# SCH-HC15C_REV3_PG3.net
KiCad netlist of a schematic drawn in Altium Designer
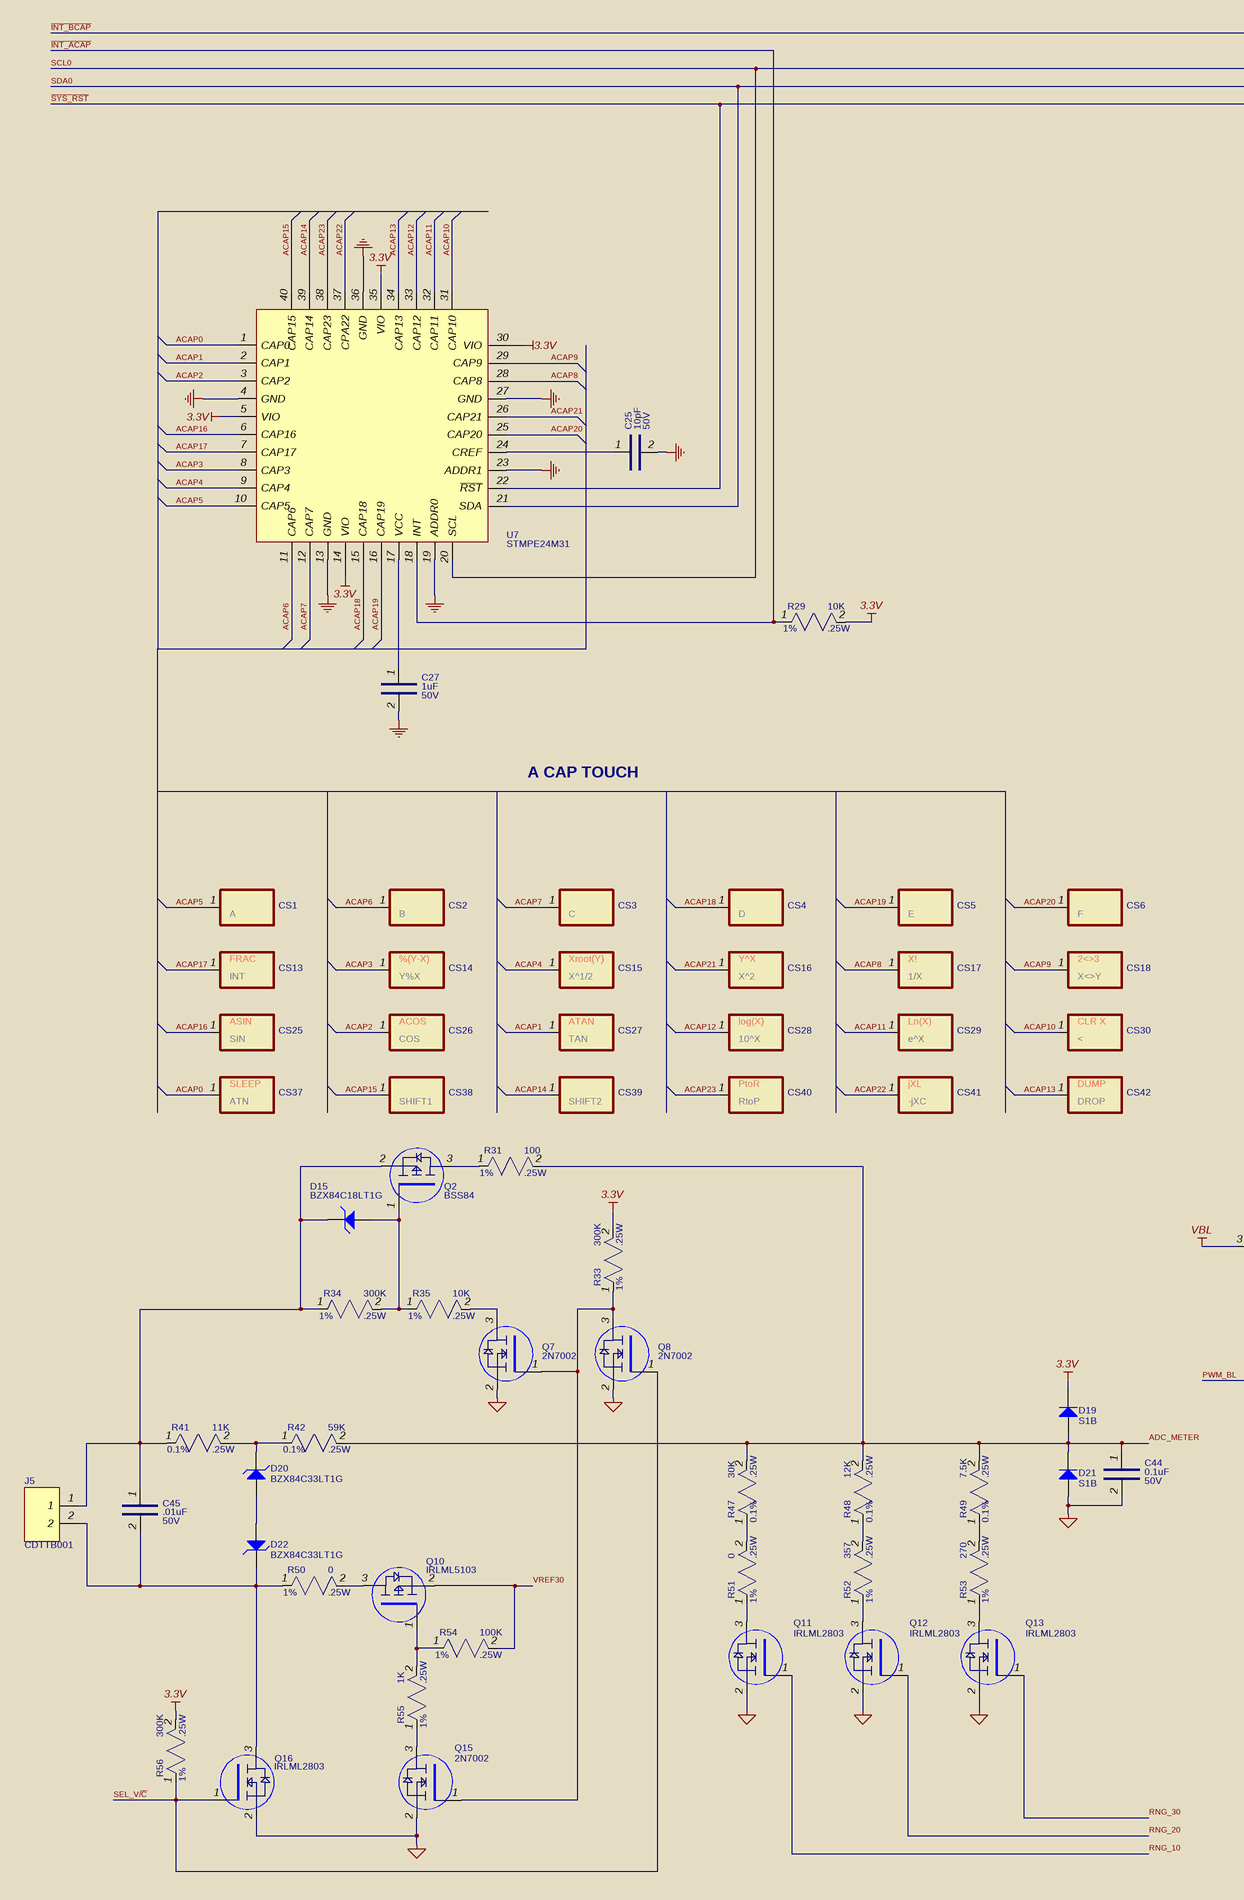
[diagram p0: SCH-HC15C_REV3_PG3.SchDoc, left]
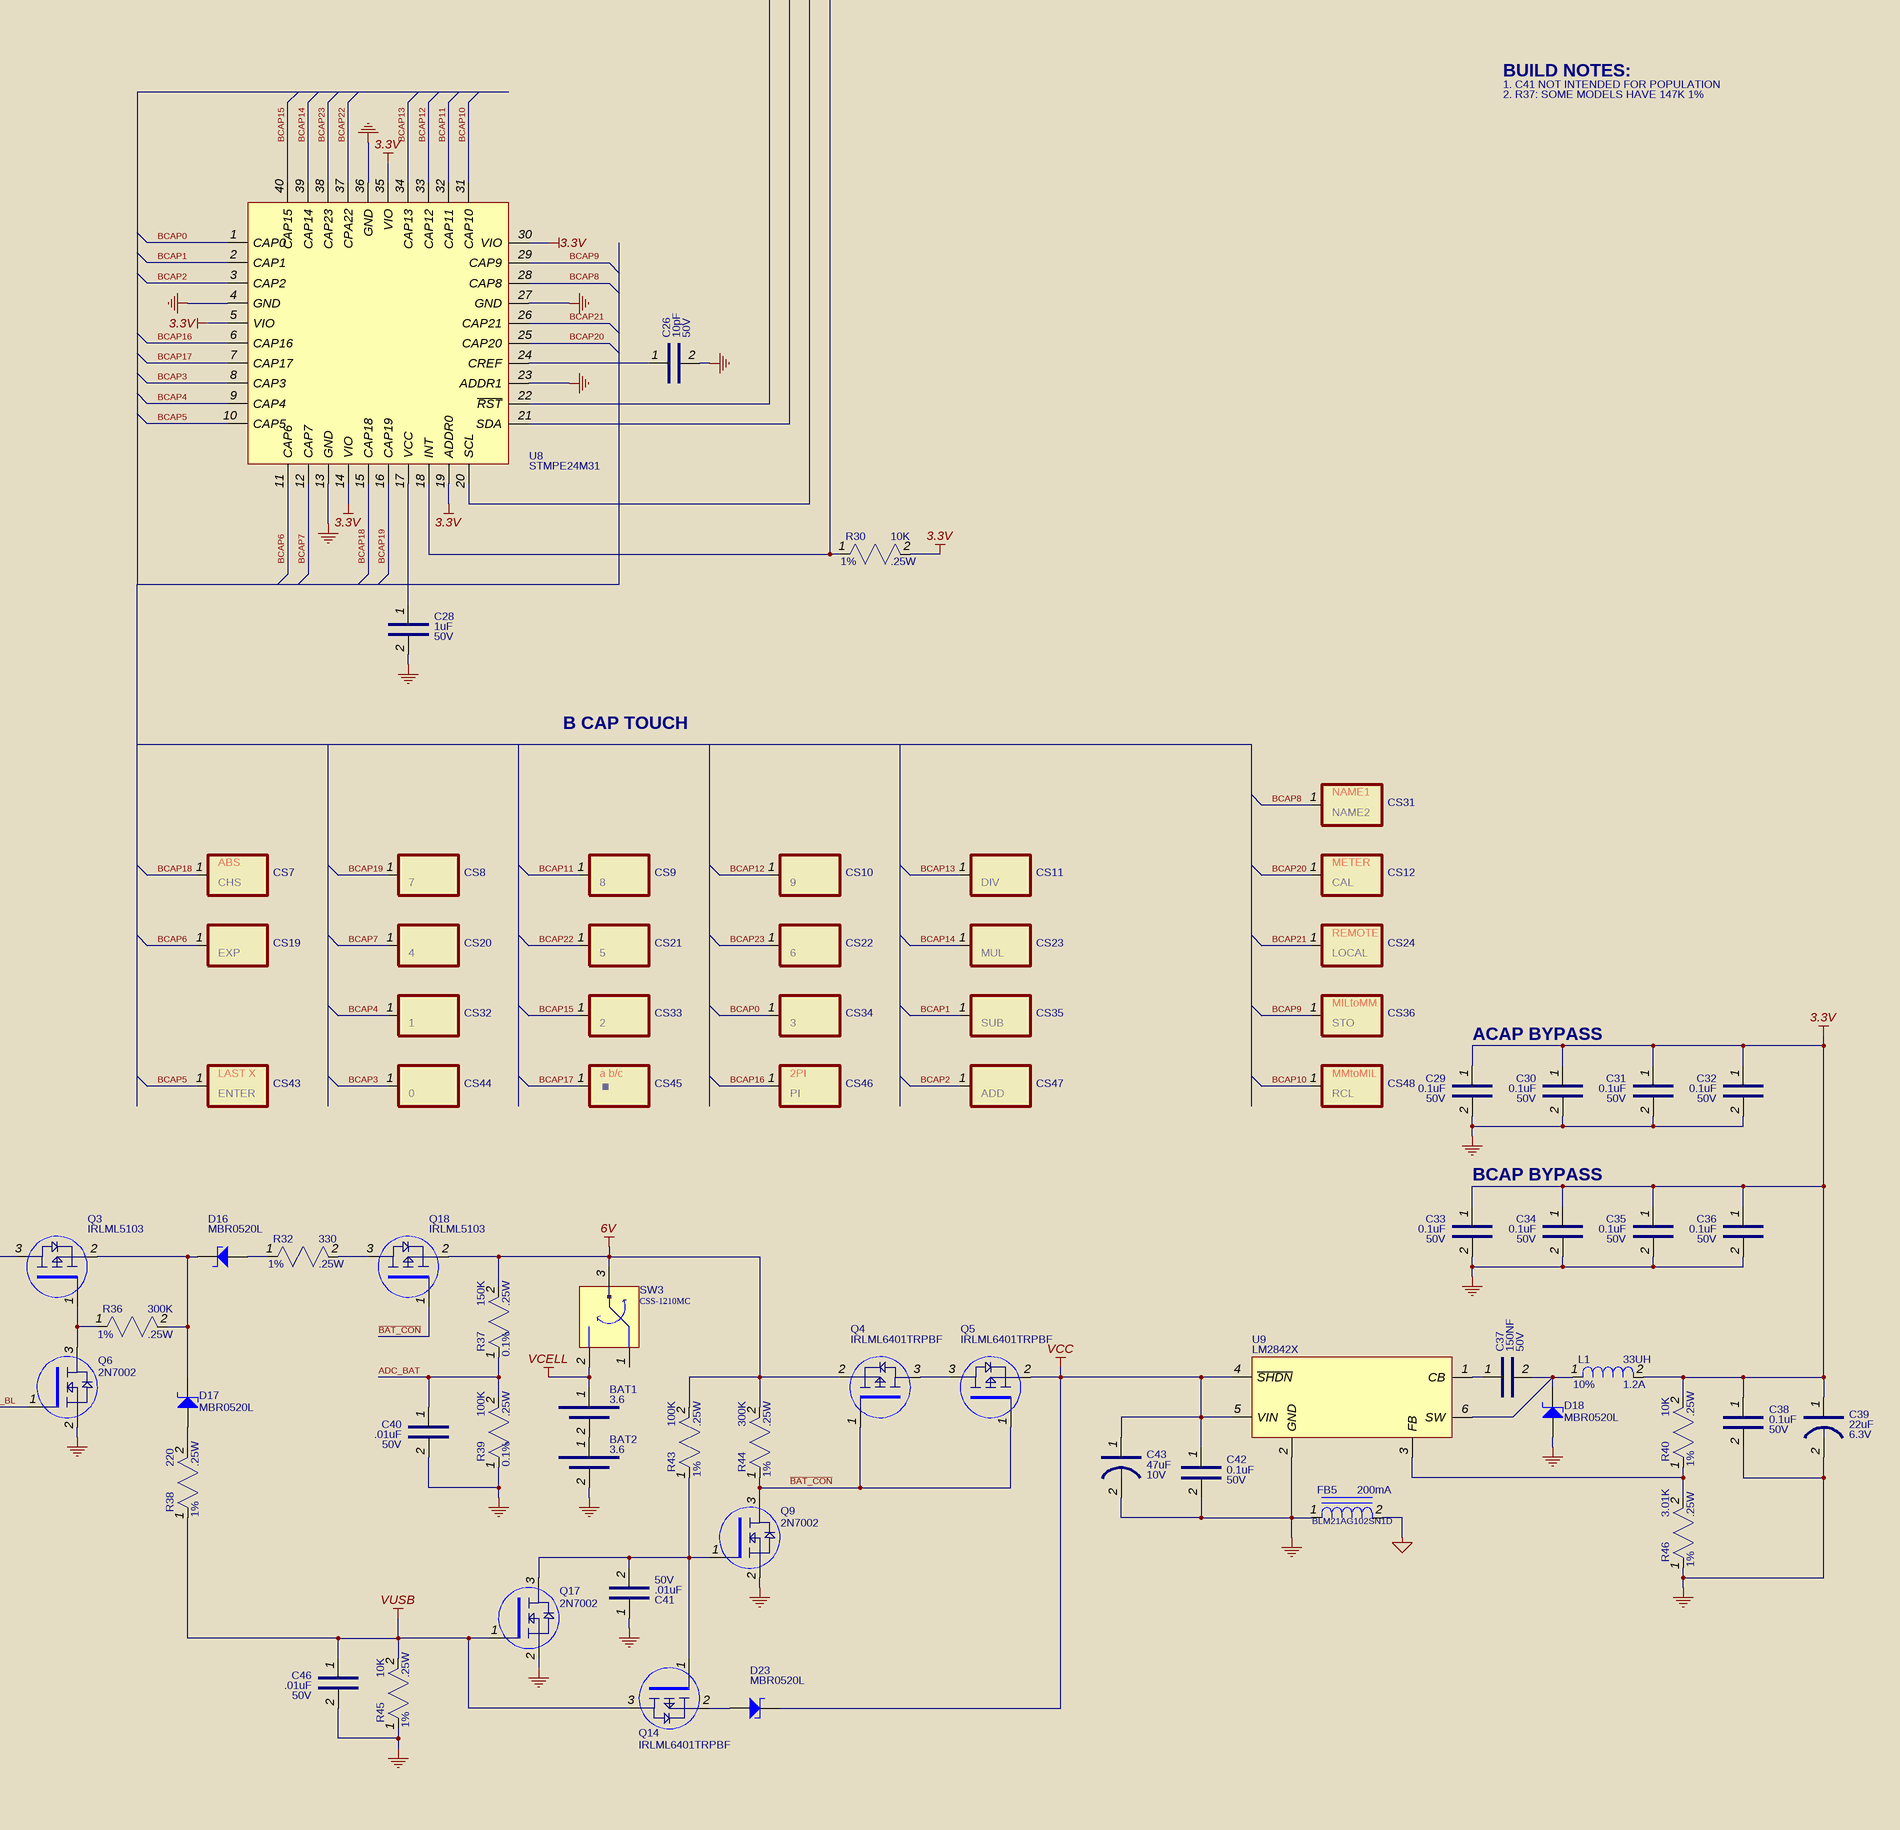
[diagram p1: SCH-HC15C_REV3_PG3.SchDoc, right]

(export (version "E")
  (design (tool "Eeschema 10.0.6"))
  (components
    (comp (ref "BAT1")
      (value "CDEVA00082_3")
      (footprint "KEYSTONE_108")
      (description "BAT HOLDER 1/2AA TH ROHS")
      (fields (field (name "MFG") "KEYSTONE") (field (name "VOLTAGE") "3.6"))
      (libsource (lib "HabLib") (part "CDEVA00082_3"))
    )
    (comp (ref "BAT2")
      (value "CDEVA00082_3")
      (footprint "KEYSTONE_108")
      (description "BAT HOLDER 1/2AA TH ROHS")
      (fields (field (name "MFG") "KEYSTONE") (field (name "VOLTAGE") "3.6"))
      (libsource (lib "HabLib") (part "CDEVA00082_3"))
    )
    (comp (ref "C25")
      (value "10pF")
      (footprint "3216[1206] - TAN COLOR")
      (description "CAP, CERAMIC, NPO, 10PF, 50V, 1206, 5%, RoHS")
      (fields (field (name "MFG") "AVX") (field (name "TOLERANCE") "10%") (field (name "VOLTAGE") "50V"))
      (libsource (lib "HabLib") (part "CDECA00143"))
    )
    (comp (ref "C26")
      (value "10pF")
      (footprint "3216[1206] - TAN COLOR")
      (description "CAP, CERAMIC, NPO, 10PF, 50V, 1206, 5%, RoHS")
      (fields (field (name "MFG") "AVX") (field (name "TOLERANCE") "10%") (field (name "VOLTAGE") "50V"))
      (libsource (lib "HabLib") (part "CDECA00143"))
    )
    (comp (ref "C27")
      (value "1uF")
      (footprint "3225[1210]")
      (description "CAP, CERAMIC CHIP 1UF 10% 50V X7R ROHS")
      (fields (field (name "MFG") "AVX") (field (name "TOLERANCE") "10%") (field (name "VOLTAGE") "50V"))
      (libsource (lib "HabLib") (part "CDECA00122"))
    )
    (comp (ref "C28")
      (value "1uF")
      (footprint "3225[1210]")
      (description "CAP, CERAMIC CHIP 1UF 10% 50V X7R ROHS")
      (fields (field (name "MFG") "AVX") (field (name "TOLERANCE") "10%") (field (name "VOLTAGE") "50V"))
      (libsource (lib "HabLib") (part "CDECA00122"))
    )
    (comp (ref "C29")
      (value "0.1uF")
      (footprint "3216[1206] - TAN COLOR")
      (description "CAP, CERAMIC CHIP 0.1UF 10% 50V X7R ROHS")
      (fields (field (name "MFG") "AVX") (field (name "TOLERANCE") "10%") (field (name "VOLTAGE") "50V"))
      (libsource (lib "HabLib") (part "CDECA00070"))
    )
    (comp (ref "C30")
      (value "0.1uF")
      (footprint "3216[1206] - TAN COLOR")
      (description "CAP, CERAMIC CHIP 0.1UF 10% 50V X7R ROHS")
      (fields (field (name "MFG") "AVX") (field (name "TOLERANCE") "10%") (field (name "VOLTAGE") "50V"))
      (libsource (lib "HabLib") (part "CDECA00070"))
    )
    (comp (ref "C31")
      (value "0.1uF")
      (footprint "3216[1206] - TAN COLOR")
      (description "CAP, CERAMIC CHIP 0.1UF 10% 50V X7R ROHS")
      (fields (field (name "MFG") "AVX") (field (name "TOLERANCE") "10%") (field (name "VOLTAGE") "50V"))
      (libsource (lib "HabLib") (part "CDECA00070"))
    )
    (comp (ref "C32")
      (value "0.1uF")
      (footprint "3216[1206] - TAN COLOR")
      (description "CAP, CERAMIC CHIP 0.1UF 10% 50V X7R ROHS")
      (fields (field (name "MFG") "AVX") (field (name "TOLERANCE") "10%") (field (name "VOLTAGE") "50V"))
      (libsource (lib "HabLib") (part "CDECA00070"))
    )
    (comp (ref "C33")
      (value "0.1uF")
      (footprint "3216[1206] - TAN COLOR")
      (description "CAP, CERAMIC CHIP 0.1UF 10% 50V X7R ROHS")
      (fields (field (name "MFG") "AVX") (field (name "TOLERANCE") "10%") (field (name "VOLTAGE") "50V"))
      (libsource (lib "HabLib") (part "CDECA00070"))
    )
    (comp (ref "C34")
      (value "0.1uF")
      (footprint "3216[1206] - TAN COLOR")
      (description "CAP, CERAMIC CHIP 0.1UF 10% 50V X7R ROHS")
      (fields (field (name "MFG") "AVX") (field (name "TOLERANCE") "10%") (field (name "VOLTAGE") "50V"))
      (libsource (lib "HabLib") (part "CDECA00070"))
    )
    (comp (ref "C35")
      (value "0.1uF")
      (footprint "3216[1206] - TAN COLOR")
      (description "CAP, CERAMIC CHIP 0.1UF 10% 50V X7R ROHS")
      (fields (field (name "MFG") "AVX") (field (name "TOLERANCE") "10%") (field (name "VOLTAGE") "50V"))
      (libsource (lib "HabLib") (part "CDECA00070"))
    )
    (comp (ref "C36")
      (value "0.1uF")
      (footprint "3216[1206] - TAN COLOR")
      (description "CAP, CERAMIC CHIP 0.1UF 10% 50V X7R ROHS")
      (fields (field (name "MFG") "AVX") (field (name "TOLERANCE") "10%") (field (name "VOLTAGE") "50V"))
      (libsource (lib "HabLib") (part "CDECA00070"))
    )
    (comp (ref "C37")
      (value "150NF")
      (footprint "3216[1206] - TAN COLOR")
      (description "CAP, CERAMIC, X7R, 150NF, 50V, 1206, 10%, RoHS")
      (fields (field (name "MFG") "KEMET") (field (name "TOLERANCE") "10%") (field (name "VOLTAGE") "50V"))
      (libsource (lib "HabLib") (part "CDECA00143_1"))
    )
    (comp (ref "C38")
      (value "0.1uF")
      (footprint "3216[1206] - TAN COLOR")
      (description "CAP, CERAMIC CHIP 0.1UF 10% 50V X7R ROHS")
      (fields (field (name "MFG") "AVX") (field (name "TOLERANCE") "10%") (field (name "VOLTAGE") "50V"))
      (libsource (lib "HabLib") (part "CDECA00070"))
    )
    (comp (ref "C39")
      (value "22uF")
      (footprint "3216[1206] - TANTALUM")
      (description "CAP, TANT, 22UF, 6.3V, 20%, LOW ESR, 1206ROHS")
      (fields (field (name "MFG") "AVX") (field (name "TOLERANCE") "20%") (field (name "VOLTAGE") "6.3V"))
      (libsource (lib "HabLib") (part "CDECA00139_1"))
    )
    (comp (ref "C40")
      (value ".01uF")
      (footprint "3216[1206] - TAN COLOR")
      (description "CAP, CERAMIC CHIP 0.01UF 10% 50V X7R ROHS")
      (fields
        (field (name "MFG") "PANASONIC")
        (field (name "TOLERANCE") "10%")
        (field (name "VOLTAGE") "50V")
      )
      (libsource (lib "HabLib") (part "CDECA00085"))
    )
    (comp (ref "C41")
      (value ".01uF")
      (footprint "3216[1206] - TAN COLOR")
      (description "CAP, CERAMIC CHIP 0.01UF 10% 50V X7R ROHS")
      (fields
        (field (name "MFG") "PANASONIC")
        (field (name "TOLERANCE") "10%")
        (field (name "VOLTAGE") "50V")
      )
      (libsource (lib "HabLib") (part "CDECA00085"))
    )
    (comp (ref "C42")
      (value "0.1uF")
      (footprint "3216[1206] - TAN COLOR")
      (description "CAP, CERAMIC CHIP 0.1UF 10% 50V X7R ROHS")
      (fields (field (name "MFG") "AVX") (field (name "TOLERANCE") "10%") (field (name "VOLTAGE") "50V"))
      (libsource (lib "HabLib") (part "CDECA00070"))
    )
    (comp (ref "C43")
      (value "47uF")
      (footprint "CAP_TANT_3528")
      (description "CAP, TANT, 47UF, 25V, 20%, 3528 ROHS")
      (fields (field (name "MFG") "AVX") (field (name "TOLERANCE") "20%") (field (name "VOLTAGE") "10V"))
      (libsource (lib "HabLib") (part "CDECA00110_1"))
    )
    (comp (ref "C44")
      (value "0.1uF")
      (footprint "3216[1206] - TAN COLOR")
      (description "CAP, CERAMIC CHIP 0.1UF 10% 50V X7R ROHS")
      (fields (field (name "MFG") "AVX") (field (name "TOLERANCE") "10%") (field (name "VOLTAGE") "50V"))
      (libsource (lib "HabLib") (part "CDECA00070"))
    )
    (comp (ref "C45")
      (value ".01uF")
      (footprint "3216[1206] - TAN COLOR")
      (description "CAP, CERAMIC CHIP 0.01UF 10% 50V X7R ROHS")
      (fields
        (field (name "MFG") "PANASONIC")
        (field (name "TOLERANCE") "10%")
        (field (name "VOLTAGE") "50V")
      )
      (libsource (lib "") (part "CDECA00085_1"))
    )
    (comp (ref "C46")
      (value ".01uF")
      (footprint "3216[1206] - TAN COLOR")
      (description "CAP, CERAMIC CHIP 0.01UF 10% 50V X7R ROHS")
      (fields
        (field (name "MFG") "PANASONIC")
        (field (name "TOLERANCE") "10%")
        (field (name "VOLTAGE") "50V")
      )
      (libsource (lib "HabLib") (part "CDECA00085"))
    )
    (comp (ref "CS1")
      (value "CAP_SENSOR")
      (footprint "CAPTOUCH1_10X10")
      (description "CAP SENSOR FOR PCB")
      (fields (field (name "VALUE2") "A") (field (name "PUBLISHER") "Altium Limited"))
      (libsource (lib "HabLib") (part "CAP_SENSOR"))
    )
    (comp (ref "CS2")
      (value "CAP_SENSOR")
      (footprint "CAPTOUCH1_10X10")
      (description "CAP SENSOR FOR PCB")
      (fields (field (name "VALUE2") "B") (field (name "PUBLISHER") "Altium Limited"))
      (libsource (lib "HabLib") (part "CAP_SENSOR"))
    )
    (comp (ref "CS3")
      (value "CAP_SENSOR")
      (footprint "CAPTOUCH1_10X10")
      (description "CAP SENSOR FOR PCB")
      (fields (field (name "VALUE2") "C") (field (name "PUBLISHER") "Altium Limited"))
      (libsource (lib "HabLib") (part "CAP_SENSOR"))
    )
    (comp (ref "CS4")
      (value "CAP_SENSOR")
      (footprint "CAPTOUCH1_10X10")
      (description "CAP SENSOR FOR PCB")
      (fields (field (name "VALUE2") "D") (field (name "PUBLISHER") "Altium Limited"))
      (libsource (lib "HabLib") (part "CAP_SENSOR"))
    )
    (comp (ref "CS5")
      (value "CAP_SENSOR")
      (footprint "CAPTOUCH1_10X10")
      (description "CAP SENSOR FOR PCB")
      (fields (field (name "VALUE2") "E") (field (name "PUBLISHER") "Altium Limited"))
      (libsource (lib "HabLib") (part "CAP_SENSOR"))
    )
    (comp (ref "CS6")
      (value "CAP_SENSOR")
      (footprint "CAPTOUCH1_10X10")
      (description "CAP SENSOR FOR PCB")
      (fields (field (name "VALUE2") "F") (field (name "PUBLISHER") "Altium Limited"))
      (libsource (lib "HabLib") (part "CAP_SENSOR"))
    )
    (comp (ref "CS7")
      (value "ABS")
      (footprint "CAPTOUCH1_10X10")
      (description "CAP SENSOR FOR PCB")
      (fields
        (field (name "VALUE2") "CHS")
        (field (name "Comment") "CAP_SENSOR")
        (field (name "PUBLISHER") "Altium Limited")
      )
      (libsource (lib "HabLib") (part "CAP_SENSOR"))
    )
    (comp (ref "CS8")
      (value "CAP_SENSOR")
      (footprint "CAPTOUCH1_10X10")
      (description "CAP SENSOR FOR PCB")
      (fields (field (name "VALUE2") "7") (field (name "PUBLISHER") "Altium Limited"))
      (libsource (lib "HabLib") (part "CAP_SENSOR"))
    )
    (comp (ref "CS9")
      (value "CAP_SENSOR")
      (footprint "CAPTOUCH1_10X10")
      (description "CAP SENSOR FOR PCB")
      (fields (field (name "VALUE2") "8") (field (name "PUBLISHER") "Altium Limited"))
      (libsource (lib "HabLib") (part "CAP_SENSOR"))
    )
    (comp (ref "CS10")
      (value "CAP_SENSOR")
      (footprint "CAPTOUCH1_10X10")
      (description "CAP SENSOR FOR PCB")
      (fields (field (name "VALUE2") "9") (field (name "PUBLISHER") "Altium Limited"))
      (libsource (lib "HabLib") (part "CAP_SENSOR"))
    )
    (comp (ref "CS11")
      (value "CAP_SENSOR")
      (footprint "CAPTOUCH1_10X10")
      (description "CAP SENSOR FOR PCB")
      (fields (field (name "VALUE2") "DIV") (field (name "PUBLISHER") "Altium Limited"))
      (libsource (lib "HabLib") (part "CAP_SENSOR"))
    )
    (comp (ref "CS12")
      (value "METER")
      (footprint "CAPTOUCH1_10X10")
      (description "CAP SENSOR FOR PCB")
      (fields
        (field (name "VALUE2") "CAL")
        (field (name "Comment") "CAP_SENSOR")
        (field (name "PUBLISHER") "Altium Limited")
      )
      (libsource (lib "HabLib") (part "CAP_SENSOR"))
    )
    (comp (ref "CS13")
      (value "FRAC")
      (footprint "CAPTOUCH1_10X10")
      (description "CAP SENSOR FOR PCB")
      (fields
        (field (name "VALUE2") "INT")
        (field (name "Comment") "CAP_SENSOR")
        (field (name "PUBLISHER") "Altium Limited")
      )
      (libsource (lib "HabLib") (part "CAP_SENSOR"))
    )
    (comp (ref "CS14")
      (value "%(Y-X)")
      (footprint "CAPTOUCH1_10X10")
      (description "CAP SENSOR FOR PCB")
      (fields
        (field (name "VALUE2") "Y%X")
        (field (name "Comment") "CAP_SENSOR")
        (field (name "PUBLISHER") "Altium Limited")
      )
      (libsource (lib "HabLib") (part "CAP_SENSOR"))
    )
    (comp (ref "CS15")
      (value "Xroot(Y)")
      (footprint "CAPTOUCH1_10X10")
      (description "CAP SENSOR FOR PCB")
      (fields
        (field (name "VALUE2") "X^1/2")
        (field (name "Comment") "CAP_SENSOR")
        (field (name "PUBLISHER") "Altium Limited")
      )
      (libsource (lib "HabLib") (part "CAP_SENSOR"))
    )
    (comp (ref "CS16")
      (value "Y^X")
      (footprint "CAPTOUCH1_10X10")
      (description "CAP SENSOR FOR PCB")
      (fields
        (field (name "VALUE2") "X^2")
        (field (name "Comment") "CAP_SENSOR")
        (field (name "PUBLISHER") "Altium Limited")
      )
      (libsource (lib "HabLib") (part "CAP_SENSOR"))
    )
    (comp (ref "CS17")
      (value "X!")
      (footprint "CAPTOUCH1_10X10")
      (description "CAP SENSOR FOR PCB")
      (fields
        (field (name "VALUE2") "1/X")
        (field (name "Comment") "CAP_SENSOR")
        (field (name "PUBLISHER") "Altium Limited")
      )
      (libsource (lib "HabLib") (part "CAP_SENSOR"))
    )
    (comp (ref "CS18")
      (value "2<>3")
      (footprint "CAPTOUCH1_10X10")
      (description "CAP SENSOR FOR PCB")
      (fields
        (field (name "VALUE2") "X<>Y")
        (field (name "Comment") "CAP_SENSOR")
        (field (name "PUBLISHER") "Altium Limited")
      )
      (libsource (lib "HabLib") (part "CAP_SENSOR"))
    )
    (comp (ref "CS19")
      (value "CAP_SENSOR")
      (footprint "CAPTOUCH1_10X10")
      (description "CAP SENSOR FOR PCB")
      (fields (field (name "VALUE2") "EXP") (field (name "PUBLISHER") "Altium Limited"))
      (libsource (lib "HabLib") (part "CAP_SENSOR"))
    )
    (comp (ref "CS20")
      (value "CAP_SENSOR")
      (footprint "CAPTOUCH1_10X10")
      (description "CAP SENSOR FOR PCB")
      (fields (field (name "VALUE2") "4") (field (name "PUBLISHER") "Altium Limited"))
      (libsource (lib "HabLib") (part "CAP_SENSOR"))
    )
    (comp (ref "CS21")
      (value "CAP_SENSOR")
      (footprint "CAPTOUCH1_10X10")
      (description "CAP SENSOR FOR PCB")
      (fields (field (name "VALUE2") "5") (field (name "PUBLISHER") "Altium Limited"))
      (libsource (lib "HabLib") (part "CAP_SENSOR"))
    )
    (comp (ref "CS22")
      (value "CAP_SENSOR")
      (footprint "CAPTOUCH1_10X10")
      (description "CAP SENSOR FOR PCB")
      (fields (field (name "VALUE2") "6") (field (name "PUBLISHER") "Altium Limited"))
      (libsource (lib "HabLib") (part "CAP_SENSOR"))
    )
    (comp (ref "CS23")
      (value "CAP_SENSOR")
      (footprint "CAPTOUCH1_10X10")
      (description "CAP SENSOR FOR PCB")
      (fields (field (name "VALUE2") "MUL") (field (name "PUBLISHER") "Altium Limited"))
      (libsource (lib "HabLib") (part "CAP_SENSOR"))
    )
    (comp (ref "CS24")
      (value "REMOTE")
      (footprint "CAPTOUCH1_10X10")
      (description "CAP SENSOR FOR PCB")
      (fields
        (field (name "VALUE2") "LOCAL")
        (field (name "Comment") "CAP_SENSOR")
        (field (name "PUBLISHER") "Altium Limited")
      )
      (libsource (lib "HabLib") (part "CAP_SENSOR"))
    )
    (comp (ref "CS25")
      (value "ASIN")
      (footprint "CAPTOUCH1_10X10")
      (description "CAP SENSOR FOR PCB")
      (fields
        (field (name "VALUE2") "SIN")
        (field (name "Comment") "CAP_SENSOR")
        (field (name "PUBLISHER") "Altium Limited")
      )
      (libsource (lib "HabLib") (part "CAP_SENSOR"))
    )
    (comp (ref "CS26")
      (value "ACOS")
      (footprint "CAPTOUCH1_10X10")
      (description "CAP SENSOR FOR PCB")
      (fields
        (field (name "VALUE2") "COS")
        (field (name "Comment") "CAP_SENSOR")
        (field (name "PUBLISHER") "Altium Limited")
      )
      (libsource (lib "HabLib") (part "CAP_SENSOR"))
    )
    (comp (ref "CS27")
      (value "ATAN")
      (footprint "CAPTOUCH1_10X10")
      (description "CAP SENSOR FOR PCB")
      (fields
        (field (name "VALUE2") "TAN")
        (field (name "Comment") "CAP_SENSOR")
        (field (name "PUBLISHER") "Altium Limited")
      )
      (libsource (lib "HabLib") (part "CAP_SENSOR"))
    )
    (comp (ref "CS28")
      (value "log(X)")
      (footprint "CAPTOUCH1_10X10")
      (description "CAP SENSOR FOR PCB")
      (fields
        (field (name "VALUE2") "10^X")
        (field (name "Comment") "CAP_SENSOR")
        (field (name "PUBLISHER") "Altium Limited")
      )
      (libsource (lib "HabLib") (part "CAP_SENSOR"))
    )
    (comp (ref "CS29")
      (value "Ln(X)")
      (footprint "CAPTOUCH1_10X10")
      (description "CAP SENSOR FOR PCB")
      (fields
        (field (name "VALUE2") "e^X")
        (field (name "Comment") "CAP_SENSOR")
        (field (name "PUBLISHER") "Altium Limited")
      )
      (libsource (lib "HabLib") (part "CAP_SENSOR"))
    )
    (comp (ref "CS30")
      (value "CLR X")
      (footprint "CAPTOUCH1_10X10")
      (description "CAP SENSOR FOR PCB")
      (fields
        (field (name "VALUE2") "<")
        (field (name "Comment") "CAP_SENSOR")
        (field (name "PUBLISHER") "Altium Limited")
      )
      (libsource (lib "HabLib") (part "CAP_SENSOR"))
    )
    (comp (ref "CS31")
      (value "NAME1")
      (footprint "CAPTOUCH1_10X10")
      (description "CAP SENSOR FOR PCB")
      (fields
        (field (name "VALUE2") "NAME2")
        (field (name "Comment") "CAP_SENSOR")
        (field (name "PUBLISHER") "Altium Limited")
      )
      (libsource (lib "HabLib") (part "CAP_SENSOR"))
    )
    (comp (ref "CS32")
      (value "CAP_SENSOR")
      (footprint "CAPTOUCH1_10X10")
      (description "CAP SENSOR FOR PCB")
      (fields (field (name "VALUE2") "1") (field (name "PUBLISHER") "Altium Limited"))
      (libsource (lib "HabLib") (part "CAP_SENSOR"))
    )
    (comp (ref "CS33")
      (value "CAP_SENSOR")
      (footprint "CAPTOUCH1_10X10")
      (description "CAP SENSOR FOR PCB")
      (fields (field (name "VALUE2") "2") (field (name "PUBLISHER") "Altium Limited"))
      (libsource (lib "HabLib") (part "CAP_SENSOR"))
    )
    (comp (ref "CS34")
      (value "CAP_SENSOR")
      (footprint "CAPTOUCH1_10X10")
      (description "CAP SENSOR FOR PCB")
      (fields (field (name "VALUE2") "3") (field (name "PUBLISHER") "Altium Limited"))
      (libsource (lib "HabLib") (part "CAP_SENSOR"))
    )
    (comp (ref "CS35")
      (value "CAP_SENSOR")
      (footprint "CAPTOUCH1_10X10")
      (description "CAP SENSOR FOR PCB")
      (fields (field (name "VALUE2") "SUB") (field (name "PUBLISHER") "Altium Limited"))
      (libsource (lib "HabLib") (part "CAP_SENSOR"))
    )
    (comp (ref "CS36")
      (value "MILtoMM")
      (footprint "CAPTOUCH1_10X10")
      (description "CAP SENSOR FOR PCB")
      (fields
        (field (name "VALUE2") "STO")
        (field (name "Comment") "CAP_SENSOR")
        (field (name "PUBLISHER") "Altium Limited")
      )
      (libsource (lib "HabLib") (part "CAP_SENSOR"))
    )
    (comp (ref "CS37")
      (value "SLEEP")
      (footprint "CAPTOUCH1_10X10")
      (description "CAP SENSOR FOR PCB")
      (fields
        (field (name "VALUE2") "ATN")
        (field (name "Comment") "CAP_SENSOR")
        (field (name "PUBLISHER") "Altium Limited")
      )
      (libsource (lib "HabLib") (part "CAP_SENSOR"))
    )
    (comp (ref "CS38")
      (value "CAP_SENSOR")
      (footprint "CAPTOUCH1_10X10")
      (description "CAP SENSOR FOR PCB")
      (fields (field (name "VALUE2") "SHIFT1") (field (name "PUBLISHER") "Altium Limited"))
      (libsource (lib "HabLib") (part "CAP_SENSOR"))
    )
    (comp (ref "CS39")
      (value "CAP_SENSOR")
      (footprint "CAPTOUCH1_10X10")
      (description "CAP SENSOR FOR PCB")
      (fields (field (name "VALUE2") "SHIFT2") (field (name "PUBLISHER") "Altium Limited"))
      (libsource (lib "HabLib") (part "CAP_SENSOR"))
    )
    (comp (ref "CS40")
      (value "PtoR")
      (footprint "CAPTOUCH1_10X10")
      (description "CAP SENSOR FOR PCB")
      (fields
        (field (name "VALUE2") "RtoP")
        (field (name "Comment") "CAP_SENSOR")
        (field (name "PUBLISHER") "Altium Limited")
      )
      (libsource (lib "HabLib") (part "CAP_SENSOR"))
    )
    (comp (ref "CS41")
      (value "jXL")
      (footprint "CAPTOUCH1_10X10")
      (description "CAP SENSOR FOR PCB")
      (fields
        (field (name "VALUE2") "-jXC")
        (field (name "Comment") "CAP_SENSOR")
        (field (name "PUBLISHER") "Altium Limited")
      )
      (libsource (lib "HabLib") (part "CAP_SENSOR"))
    )
    (comp (ref "CS42")
      (value "DUMP")
      (footprint "CAPTOUCH1_10X10")
      (description "CAP SENSOR FOR PCB")
      (fields
        (field (name "VALUE2") "DROP")
        (field (name "Comment") "CAP_SENSOR")
        (field (name "PUBLISHER") "Altium Limited")
      )
      (libsource (lib "HabLib") (part "CAP_SENSOR"))
    )
    (comp (ref "CS43")
      (value "LAST X")
      (footprint "CAPTOUCH1_10X23")
      (description "CAP SENSOR FOR PCB")
      (fields
        (field (name "VALUE2") "ENTER")
        (field (name "Comment") "CAP_SENSOR_ENT")
        (field (name "PUBLISHER") "Altium Limited")
      )
      (libsource (lib "HabLib") (part "CAP_SENSOR_ENT"))
    )
    (comp (ref "CS44")
      (value "CAP_SENSOR")
      (footprint "CAPTOUCH1_10X10")
      (description "CAP SENSOR FOR PCB")
      (fields (field (name "VALUE2") "0") (field (name "PUBLISHER") "Altium Limited"))
      (libsource (lib "HabLib") (part "CAP_SENSOR"))
    )
    (comp (ref "CS45")
      (value "a b/c")
      (footprint "CAPTOUCH1_10X10")
      (description "CAP SENSOR FOR PCB")
      (fields
        (field (name "VALUE2") ".")
        (field (name "Comment") "CAP_SENSOR")
        (field (name "PUBLISHER") "Altium Limited")
      )
      (libsource (lib "HabLib") (part "CAP_SENSOR"))
    )
    (comp (ref "CS46")
      (value "2PI")
      (footprint "CAPTOUCH1_10X10")
      (description "CAP SENSOR FOR PCB")
      (fields
        (field (name "VALUE2") "PI")
        (field (name "Comment") "CAP_SENSOR")
        (field (name "PUBLISHER") "Altium Limited")
      )
      (libsource (lib "HabLib") (part "CAP_SENSOR"))
    )
    (comp (ref "CS47")
      (value "CAP_SENSOR")
      (footprint "CAPTOUCH1_10X10")
      (description "CAP SENSOR FOR PCB")
      (fields (field (name "VALUE2") "ADD") (field (name "PUBLISHER") "Altium Limited"))
      (libsource (lib "HabLib") (part "CAP_SENSOR"))
    )
    (comp (ref "CS48")
      (value "MMtoMIL")
      (footprint "CAPTOUCH1_10X10")
      (description "CAP SENSOR FOR PCB")
      (fields
        (field (name "VALUE2") "RCL")
        (field (name "Comment") "CAP_SENSOR")
        (field (name "PUBLISHER") "Altium Limited")
      )
      (libsource (lib "HabLib") (part "CAP_SENSOR"))
    )
    (comp (ref "D15")
      (value "BZX84C18LT1G")
      (footprint "SOT23 - TRANSISTOR")
      (description "DIODE, ZENER, 18V, 225MW, SOT-23, ROHS")
      (fields (field (name "MFG") "ON SEMICONDUCTOR") (field (name "Comment") "CDEDA00055_1"))
      (libsource (lib "HabLib") (part "CDEDA00055_1"))
    )
    (comp (ref "D16")
      (value "MBR0520L")
      (footprint "SOD123")
      (description "Diode, Schottky rectifier, 20V, 0.5A, SOD-123 package, Pb free")
      (fields (field (name "MFG") "FAIRCHILD SEMI") (field (name "Comment") "CDEDA00019_1"))
      (libsource (lib "HabLib") (part "CDEDA00019_1"))
    )
    (comp (ref "D17")
      (value "MBR0520L")
      (footprint "SOD123")
      (description "Diode, Schottky rectifier, 20V, 0.5A, SOD-123 package, Pb free")
      (fields (field (name "MFG") "FAIRCHILD SEMI") (field (name "Comment") "CDEDA00019_1"))
      (libsource (lib "HabLib") (part "CDEDA00019_1"))
    )
    (comp (ref "D18")
      (value "MBR0520L")
      (footprint "SOD123")
      (description "Diode, Schottky rectifier, 20V, 0.5A, SOD-123 package, Pb free")
      (fields (field (name "MFG") "FAIRCHILD SEMI") (field (name "Comment") "CDEDA00019_1"))
      (libsource (lib "HabLib") (part "CDEDA00019_1"))
    )
    (comp (ref "D19")
      (value "S1B")
      (footprint "DIODE SMA")
      (description "DIODE, 1A, 100V, SMA, ROHS")
      (fields (field (name "MFG") "FAIRCHILD SEMICONDUCTOR") (field (name "Comment") "CDEDA00055_3"))
      (libsource (lib "HabLib") (part "CDEDA00055_3"))
    )
    (comp (ref "D20")
      (value "BZX84C33LT1G")
      (footprint "SOT23 - TRANSISTOR")
      (description "DIODE, ZENER, 33V, 225MW, SOT-23, ROHS")
      (fields (field (name "MFG") "ON SEMICONDUCTOR") (field (name "Comment") "CDEDA00055_2"))
      (libsource (lib "HabLib") (part "CDEDA00055_2"))
    )
    (comp (ref "D21")
      (value "S1B")
      (footprint "DIODE SMA")
      (description "DIODE, 1A, 100V, SMA, ROHS")
      (fields (field (name "MFG") "FAIRCHILD SEMICONDUCTOR") (field (name "Comment") "CDEDA00055_3"))
      (libsource (lib "HabLib") (part "CDEDA00055_3"))
    )
    (comp (ref "D22")
      (value "BZX84C33LT1G")
      (footprint "SOT23 - TRANSISTOR")
      (description "DIODE, ZENER, 33V, 225MW, SOT-23, ROHS")
      (fields (field (name "MFG") "ON SEMICONDUCTOR") (field (name "Comment") "CDEDA00055_2"))
      (libsource (lib "HabLib") (part "CDEDA00055_2"))
    )
    (comp (ref "D23")
      (value "MBR0520L")
      (footprint "SOD123")
      (description "Diode, Schottky rectifier, 20V, 0.5A, SOD-123 package, Pb free")
      (fields (field (name "MFG") "FAIRCHILD SEMI") (field (name "Comment") "CDEDA00019_1"))
      (libsource (lib "HabLib") (part "CDEDA00019_1"))
    )
    (comp (ref "FB5")
      (value "CDEVA00115")
      (footprint "2012[0805]")
      (description "FERRITE, 1KOHM AT 100MHZ, 220MA, .450DCR")
      (fields
        (field (name "MFG") "MURATA")
        (field (name "TOLERANCE") "10%")
        (field (name "MFG_PN") "BLM21AG102SN1D")
        (field (name "POWER") "200mA")
        (field (name "PUBLISHER") "Altium Limited")
      )
      (libsource (lib "HabLib") (part "CDEVA00115"))
    )
    (comp (ref "J5")
      (value "CDTTB001")
      (footprint "PHOENIX_CONTACT_1933189")
      (description "CONN, HDR, 2PIN, 5MM PHONIX CONTACT, ROHS")
      (fields (field (name "MFG") "PHOENIX CONTACT"))
      (libsource (lib "HabLib") (part "CDTTB001"))
    )
    (comp (ref "L1")
      (value "33UH")
      (footprint "BOURNS_SDR0805-XXXX")
      (description "INDUCTOR, 33UH, 10%, SMT, NON-SHIELDED, FERRITE CORE, ROHS")
      (fields
        (field (name "MFG") "BOURNS")
        (field (name "TOLERANCE") "10%")
        (field (name "POWER") "1.2A")
        (field (name "Comment") "CDEHA00005_1")
      )
      (libsource (lib "HabLib") (part "CDEHA00005_1"))
    )
    (comp (ref "Q2")
      (value "BSS84")
      (footprint "SOT23 - TRANSISTOR")
      (description "MOSFET P CHN, VDS=50V, RDSON = 10OHM, SOT 23")
      (fields
        (field (name "MFG") "DIODES INC")
        (field (name "Comment") "CDENA00031_1")
        (field (name "PUBLISHER") "Altium Limited")
      )
      (libsource (lib "HabLib") (part "CDENA00031_1"))
    )
    (comp (ref "Q3")
      (value "IRLML5103")
      (footprint "SOT23 - TRANSISTOR")
      (description "MOSFET P CHN, VDS=30V, RDSON = .6OHM, SOT 23")
      (fields
        (field (name "MFG") "INTERNATIONAL RECTIFIER")
        (field (name "Comment") "CDENA00031")
        (field (name "PUBLISHER") "Altium Limited")
      )
      (libsource (lib "HabLib") (part "CDENA00031"))
    )
    (comp (ref "Q4")
      (value "IRLML6401TRPBF")
      (footprint "SOT23 - TRANSISTOR")
      (description "MOSFET P CHN, VDS=12V, RDSON = .05OHM, SOT 23")
      (fields
        (field (name "MFG") "INTERNATIONAL RECTIFIER")
        (field (name "Comment") "CDENA00031_3")
        (field (name "PUBLISHER") "Altium Limited")
      )
      (libsource (lib "HabLib") (part "CDENA00031_3"))
    )
    (comp (ref "Q5")
      (value "IRLML6401TRPBF")
      (footprint "SOT23 - TRANSISTOR")
      (description "MOSFET P CHN, VDS=12V, RDSON = .05OHM, SOT 23")
      (fields
        (field (name "MFG") "INTERNATIONAL RECTIFIER")
        (field (name "Comment") "CDENA00031_3")
        (field (name "PUBLISHER") "Altium Limited")
      )
      (libsource (lib "") (part "CDENA00031_3_1"))
    )
    (comp (ref "Q6")
      (value "2N7002")
      (footprint "SOT23 - TRANSISTOR")
      (description "MOSFET N CHN, VDS=60V, 115 mA, SOT 23")
      (fields
        (field (name "MFG") "DIODES INC")
        (field (name "Comment") "CDENA00030")
        (field (name "PUBLISHER") "Altium Limited")
      )
      (libsource (lib "") (part "CDENA00030_1"))
    )
    (comp (ref "Q7")
      (value "2N7002")
      (footprint "SOT23 - TRANSISTOR")
      (description "MOSFET N CHN, VDS=60V, 115 mA, SOT 23")
      (fields
        (field (name "MFG") "DIODES INC")
        (field (name "Comment") "CDENA00030")
        (field (name "PUBLISHER") "Altium Limited")
      )
      (libsource (lib "HabLib") (part "CDENA00030"))
    )
    (comp (ref "Q8")
      (value "2N7002")
      (footprint "SOT23 - TRANSISTOR")
      (description "MOSFET N CHN, VDS=60V, 115 mA, SOT 23")
      (fields
        (field (name "MFG") "DIODES INC")
        (field (name "Comment") "CDENA00030")
        (field (name "PUBLISHER") "Altium Limited")
      )
      (libsource (lib "HabLib") (part "CDENA00030"))
    )
    (comp (ref "Q9")
      (value "2N7002")
      (footprint "SOT23 - TRANSISTOR")
      (description "MOSFET N CHN, VDS=60V, 115 mA, SOT 23")
      (fields
        (field (name "MFG") "DIODES INC")
        (field (name "Comment") "CDENA00030")
        (field (name "PUBLISHER") "Altium Limited")
      )
      (libsource (lib "") (part "CDENA00030_1"))
    )
    (comp (ref "Q10")
      (value "IRLML5103")
      (footprint "SOT23 - TRANSISTOR")
      (description "MOSFET P CHN, VDS=30V, RDSON = .6OHM, SOT 23")
      (fields
        (field (name "MFG") "INTERNATIONAL RECTIFIER")
        (field (name "Comment") "CDENA00031")
        (field (name "PUBLISHER") "Altium Limited")
      )
      (libsource (lib "HabLib") (part "CDENA00031"))
    )
    (comp (ref "Q11")
      (value "IRLML2803")
      (footprint "SOT23 - TRANSISTOR")
      (description "MOSFET N CHN, VDS=60V, 115 mA, SOT 23")
      (fields
        (field (name "MFG") "INTERNATIONAL RECTIFIER")
        (field (name "Comment") "CDENA00031_2")
        (field (name "PUBLISHER") "Altium Limited")
      )
      (libsource (lib "") (part "CDENA00031_2_1"))
    )
    (comp (ref "Q12")
      (value "IRLML2803")
      (footprint "SOT23 - TRANSISTOR")
      (description "MOSFET N CHN, VDS=60V, 115 mA, SOT 23")
      (fields
        (field (name "MFG") "INTERNATIONAL RECTIFIER")
        (field (name "Comment") "CDENA00031_2")
        (field (name "PUBLISHER") "Altium Limited")
      )
      (libsource (lib "") (part "CDENA00031_2_1"))
    )
    (comp (ref "Q13")
      (value "IRLML2803")
      (footprint "SOT23 - TRANSISTOR")
      (description "MOSFET N CHN, VDS=60V, 115 mA, SOT 23")
      (fields
        (field (name "MFG") "INTERNATIONAL RECTIFIER")
        (field (name "Comment") "CDENA00031_2")
        (field (name "PUBLISHER") "Altium Limited")
      )
      (libsource (lib "") (part "CDENA00031_2_1"))
    )
    (comp (ref "Q14")
      (value "IRLML6401TRPBF")
      (footprint "SOT23 - TRANSISTOR")
      (description "MOSFET P CHN, VDS=12V, RDSON = .05OHM, SOT 23")
      (fields
        (field (name "MFG") "INTERNATIONAL RECTIFIER")
        (field (name "Comment") "CDENA00031_3")
        (field (name "PUBLISHER") "Altium Limited")
      )
      (libsource (lib "HabLib") (part "CDENA00031_3"))
    )
    (comp (ref "Q15")
      (value "2N7002")
      (footprint "SOT23 - TRANSISTOR")
      (description "MOSFET N CHN, VDS=60V, 115 mA, SOT 23")
      (fields
        (field (name "MFG") "DIODES INC")
        (field (name "Comment") "CDENA00030")
        (field (name "PUBLISHER") "Altium Limited")
      )
      (libsource (lib "HabLib") (part "CDENA00030"))
    )
    (comp (ref "Q16")
      (value "IRLML2803")
      (footprint "SOT23 - TRANSISTOR")
      (description "MOSFET N CHN, VDS=60V, 115 mA, SOT 23")
      (fields
        (field (name "MFG") "INTERNATIONAL RECTIFIER")
        (field (name "Comment") "CDENA00031_2")
        (field (name "PUBLISHER") "Altium Limited")
      )
      (libsource (lib "HabLib") (part "CDENA00031_2"))
    )
    (comp (ref "Q17")
      (value "2N7002")
      (footprint "SOT23 - TRANSISTOR")
      (description "MOSFET N CHN, VDS=60V, 115 mA, SOT 23")
      (fields
        (field (name "MFG") "DIODES INC")
        (field (name "Comment") "CDENA00030")
        (field (name "PUBLISHER") "Altium Limited")
      )
      (libsource (lib "") (part "CDENA00030_1"))
    )
    (comp (ref "Q18")
      (value "IRLML5103")
      (footprint "SOT23 - TRANSISTOR")
      (description "MOSFET P CHN, VDS=30V, RDSON = .6OHM, SOT 23")
      (fields
        (field (name "MFG") "INTERNATIONAL RECTIFIER")
        (field (name "Comment") "CDENA00031")
        (field (name "PUBLISHER") "Altium Limited")
      )
      (libsource (lib "HabLib") (part "CDENA00031"))
    )
    (comp (ref "R29")
      (value "10K")
      (footprint "HabLib:3216[1206]")
      (description "RESISTOR, CHIP 1206 10K OHM 1% 1/4W THICK FILM ROHS")
      (fields
        (field (name "MFG") "PANASONIC")
        (field (name "TOLERANCE") "1%")
        (field (name "POWER") ".25W")
        (field (name "Comment") "CDERA00170")
        (field (name "PUBLISHER") "Altium Limited")
      )
      (libsource (lib "HabLib") (part "CDERA00170"))
    )
    (comp (ref "R30")
      (value "10K")
      (footprint "HabLib:3216[1206]")
      (description "RESISTOR, CHIP 1206 10K OHM 1% 1/4W THICK FILM ROHS")
      (fields
        (field (name "MFG") "PANASONIC")
        (field (name "TOLERANCE") "1%")
        (field (name "POWER") ".25W")
        (field (name "Comment") "CDERA00170")
        (field (name "PUBLISHER") "Altium Limited")
      )
      (libsource (lib "HabLib") (part "CDERA00170"))
    )
    (comp (ref "R31")
      (value "100")
      (footprint "HabLib:3216[1206]")
      (description "RESISTOR, CHIP 1206 100 OHM 1% 1/4W THICK FILM ROHS")
      (fields
        (field (name "MFG") "PANASONIC")
        (field (name "TOLERANCE") "1%")
        (field (name "POWER") ".25W")
        (field (name "Comment") "CDERA00176")
        (field (name "PUBLISHER") "Altium Limited")
      )
      (libsource (lib "HabLib") (part "CDERA00176"))
    )
    (comp (ref "R32")
      (value "330")
      (footprint "HABLIB:3216[1206]")
      (description "RESISTOR, CHIP 1206 330 OHM 1% 1/4W THICK FILM ROHS")
      (fields
        (field (name "MFG") "PANASONIC")
        (field (name "TOLERANCE") "1%")
        (field (name "POWER") ".25W")
        (field (name "Comment") "CDERA00154")
        (field (name "PUBLISHER") "Altium Limited")
      )
      (libsource (lib "HabLib") (part "CDERA00154"))
    )
    (comp (ref "R33")
      (value "300K")
      (footprint "HABLIB:3216[1206]")
      (description "RESISTOR, CHIP 1206 300K OHM 1% 1/4W THICK FILM ROHS")
      (fields
        (field (name "MFG") "PANASONIC")
        (field (name "TOLERANCE") "1%")
        (field (name "POWER") ".25W")
        (field (name "Comment") "CDERA00275_8")
        (field (name "PUBLISHER") "Altium Limited")
      )
      (libsource (lib "HabLib") (part "CDERA00275_8"))
    )
    (comp (ref "R34")
      (value "300K")
      (footprint "HABLIB:3216[1206]")
      (description "RESISTOR, CHIP 1206 300K OHM 1% 1/4W THICK FILM ROHS")
      (fields
        (field (name "MFG") "PANASONIC")
        (field (name "TOLERANCE") "1%")
        (field (name "POWER") ".25W")
        (field (name "Comment") "CDERA00275_8")
        (field (name "PUBLISHER") "Altium Limited")
      )
      (libsource (lib "HabLib") (part "CDERA00275_8"))
    )
    (comp (ref "R35")
      (value "10K")
      (footprint "HabLib:3216[1206]")
      (description "RESISTOR, CHIP 1206 10K OHM 1% 1/4W THICK FILM ROHS")
      (fields
        (field (name "MFG") "PANASONIC")
        (field (name "TOLERANCE") "1%")
        (field (name "POWER") ".25W")
        (field (name "Comment") "CDERA00170")
        (field (name "PUBLISHER") "Altium Limited")
      )
      (libsource (lib "HabLib") (part "CDERA00170"))
    )
    (comp (ref "R36")
      (value "300K")
      (footprint "HABLIB:3216[1206]")
      (description "RESISTOR, CHIP 1206 300K OHM 1% 1/4W THICK FILM ROHS")
      (fields
        (field (name "MFG") "PANASONIC")
        (field (name "TOLERANCE") "1%")
        (field (name "POWER") ".25W")
        (field (name "Comment") "CDERA00275_8")
        (field (name "PUBLISHER") "Altium Limited")
      )
      (libsource (lib "HabLib") (part "CDERA00275_8"))
    )
    (comp (ref "R37")
      (value "150K")
      (footprint "HABLIB:3216[1206]")
      (description "RESISTOR, CHIP 1206 150K OHM 0.1% 1/4W THIN FILM ROHS")
      (fields
        (field (name "MFG") "VISHAY")
        (field (name "TOLERANCE") "0.1%")
        (field (name "POWER") ".25W")
        (field (name "Comment") "CDERA00276_9")
        (field (name "PUBLISHER") "Altium Limited")
      )
      (libsource (lib "HabLib") (part "CDERA00276_9"))
    )
    (comp (ref "R38")
      (value "220")
      (footprint "HABLIB:3216[1206]")
      (description "RESISTOR, CHIP 1206 220 OHM 1% 1/4W THICK FILM ROHS")
      (fields
        (field (name "MFG") "PANASONIC")
        (field (name "TOLERANCE") "1%")
        (field (name "POWER") ".25W")
        (field (name "Comment") "CDERA00273_2")
        (field (name "PUBLISHER") "Altium Limited")
      )
      (libsource (lib "HabLib") (part "CDERA00273_2"))
    )
    (comp (ref "R39")
      (value "100K")
      (footprint "HABLIB:3216[1206]")
      (description "RESISTOR, CHIP 1206 100K OHM 0.1% 1/4W THIN FILM ROHS")
      (fields
        (field (name "MFG") "BOURNS")
        (field (name "TOLERANCE") "0.1%")
        (field (name "POWER") ".25W")
        (field (name "Comment") "CDERA00198_1")
        (field (name "PUBLISHER") "Altium Limited")
      )
      (libsource (lib "HabLib") (part "CDERA00198_1"))
    )
    (comp (ref "R40")
      (value "10K")
      (footprint "HabLib:3216[1206]")
      (description "RESISTOR, CHIP 1206 10K OHM 1% 1/4W THICK FILM ROHS")
      (fields
        (field (name "MFG") "PANASONIC")
        (field (name "TOLERANCE") "1%")
        (field (name "POWER") ".25W")
        (field (name "Comment") "CDERA00170")
        (field (name "PUBLISHER") "Altium Limited")
      )
      (libsource (lib "HabLib") (part "CDERA00170"))
    )
    (comp (ref "R41")
      (value "11K")
      (footprint "HABLIB:3216[1206]")
      (description "RESISTOR, CHIP 1206 11K OHM 0.1% 1/4W THICK FILM ROHS")
      (fields
        (field (name "MFG") "SUSUMU")
        (field (name "TOLERANCE") "0.1%")
        (field (name "POWER") ".25W")
        (field (name "Comment") "CDERA00276_5")
        (field (name "PUBLISHER") "Altium Limited")
      )
      (libsource (lib "HabLib") (part "CDERA00276_5"))
    )
    (comp (ref "R42")
      (value "59K")
      (footprint "HABLIB:3216[1206]")
      (description "RESISTOR, CHIP 1206 59K OHM 0.1% 1/4W THICK FILM ROHS")
      (fields
        (field (name "MFG") "SUSUMU")
        (field (name "TOLERANCE") "0.1%")
        (field (name "POWER") ".25W")
        (field (name "Comment") "CDERA00276_6")
        (field (name "PUBLISHER") "Altium Limited")
      )
      (libsource (lib "HabLib") (part "CDERA00276_6"))
    )
    (comp (ref "R43")
      (value "100K")
      (footprint "HABLIB:3216[1206]")
      (description "RESISTOR, CHIP 1206 100K OHM 1% 1/4W THICK FILM ROHS")
      (fields
        (field (name "MFG") "PANASONIC")
        (field (name "TOLERANCE") "1%")
        (field (name "POWER") ".25W")
        (field (name "Comment") "CDERA00198")
        (field (name "PUBLISHER") "Altium Limited")
      )
      (libsource (lib "HabLib") (part "CDERA00198"))
    )
    (comp (ref "R44")
      (value "300K")
      (footprint "HABLIB:3216[1206]")
      (description "RESISTOR, CHIP 1206 300K OHM 1% 1/4W THICK FILM ROHS")
      (fields
        (field (name "MFG") "PANASONIC")
        (field (name "TOLERANCE") "1%")
        (field (name "POWER") ".25W")
        (field (name "Comment") "CDERA00275_8")
        (field (name "PUBLISHER") "Altium Limited")
      )
      (libsource (lib "HabLib") (part "CDERA00275_8"))
    )
    (comp (ref "R45")
      (value "10K")
      (footprint "HabLib:3216[1206]")
      (description "RESISTOR, CHIP 1206 10K OHM 1% 1/4W THICK FILM ROHS")
      (fields
        (field (name "MFG") "PANASONIC")
        (field (name "TOLERANCE") "1%")
        (field (name "POWER") ".25W")
        (field (name "Comment") "CDERA00170")
        (field (name "PUBLISHER") "Altium Limited")
      )
      (libsource (lib "HabLib") (part "CDERA00170"))
    )
    (comp (ref "R46")
      (value "3.01K")
      (footprint "3216[1206]")
      (description "RESISTOR, CHIP 1206 3.01K OHM 1% 1/4W THICK FILM ROHS")
      (fields
        (field (name "MFG") "PANASONIC")
        (field (name "TOLERANCE") "1%")
        (field (name "POWER") ".25W")
        (field (name "Comment") "CDERA00276_3")
      )
      (libsource (lib "HabLib") (part "CDERA00276_3"))
    )
    (comp (ref "R47")
      (value "30K")
      (footprint "HABLIB:3216[1206]")
      (description "RESISTOR, CHIP 1206 30K OHM 0.1% 1/4W THIN FILM ROHS")
      (fields
        (field (name "MFG") "SUSUMU")
        (field (name "TOLERANCE") "0.1%")
        (field (name "POWER") ".25W")
        (field (name "Comment") "CDERA00276_4")
        (field (name "PUBLISHER") "Altium Limited")
      )
      (libsource (lib "HabLib") (part "CDERA00276_4"))
    )
    (comp (ref "R48")
      (value "12K")
      (footprint "HABLIB:3216[1206]")
      (description "RESISTOR, CHIP 1206 12K OHM 0.1% 1/4W THICK FILM ROHS")
      (fields
        (field (name "MFG") "VISHAY")
        (field (name "TOLERANCE") "0.1%")
        (field (name "POWER") ".25W")
        (field (name "Comment") "CDERA00276_7")
        (field (name "PUBLISHER") "Altium Limited")
      )
      (libsource (lib "HabLib") (part "CDERA00276_7"))
    )
    (comp (ref "R49")
      (value "7.5K")
      (footprint "HABLIB:3216[1206]")
      (description "RESISTOR, CHIP 1206 7.5K OHM 0.1% 1/4W THICK FILM ROHS")
      (fields
        (field (name "MFG") "VISHAY")
        (field (name "TOLERANCE") "0.1%")
        (field (name "POWER") ".25W")
        (field (name "Comment") "CDERA00276_8")
        (field (name "PUBLISHER") "Altium Limited")
      )
      (libsource (lib "HabLib") (part "CDERA00276_8"))
    )
    (comp (ref "R50")
      (value "0")
      (footprint "HABLIB:3216[1206]")
      (description "RESISTOR, CHIP 1206 0.0 OHM 1% 1/4W THICK FILM ROHS")
      (fields
        (field (name "MFG") "PANASONIC")
        (field (name "TOLERANCE") "1%")
        (field (name "POWER") ".25W")
        (field (name "Comment") "CDERA00181")
        (field (name "PUBLISHER") "Altium Limited")
      )
      (libsource (lib "HabLib") (part "CDERA00181"))
    )
    (comp (ref "R51")
      (value "0")
      (footprint "HABLIB:3216[1206]")
      (description "RESISTOR, CHIP 1206 0.0 OHM 1% 1/4W THICK FILM ROHS")
      (fields
        (field (name "MFG") "PANASONIC")
        (field (name "TOLERANCE") "1%")
        (field (name "POWER") ".25W")
        (field (name "Comment") "CDERA00181")
        (field (name "PUBLISHER") "Altium Limited")
      )
      (libsource (lib "HabLib") (part "CDERA00181"))
    )
    (comp (ref "R52")
      (value "357")
      (footprint "HABLIB:3216[1206]")
      (description "RESISTOR, CHIP 1206 357 OHM 1% 1/4W THICK FILM ROHS")
      (fields
        (field (name "MFG") "PANASONIC")
        (field (name "TOLERANCE") "1%")
        (field (name "POWER") ".25W")
        (field (name "Comment") "CDERA00275_6")
        (field (name "PUBLISHER") "Altium Limited")
      )
      (libsource (lib "HabLib") (part "CDERA00275_6"))
    )
    (comp (ref "R53")
      (value "270")
      (footprint "HABLIB:3216[1206]")
      (description "RESISTOR, CHIP 1206 270 OHM 1% 1/4W THICK FILM ROHS")
      (fields
        (field (name "MFG") "PANASONIC")
        (field (name "TOLERANCE") "1%")
        (field (name "POWER") ".25W")
        (field (name "Comment") "CDERA00209")
        (field (name "PUBLISHER") "Altium Limited")
      )
      (libsource (lib "HabLib") (part "CDERA00209"))
    )
    (comp (ref "R54")
      (value "100K")
      (footprint "HABLIB:3216[1206]")
      (description "RESISTOR, CHIP 1206 100K OHM 1% 1/4W THICK FILM ROHS")
      (fields
        (field (name "MFG") "PANASONIC")
        (field (name "TOLERANCE") "1%")
        (field (name "POWER") ".25W")
        (field (name "Comment") "CDERA00198")
        (field (name "PUBLISHER") "Altium Limited")
      )
      (libsource (lib "HabLib") (part "CDERA00198"))
    )
    (comp (ref "R55")
      (value "1K")
      (footprint "HABLIB:3216[1206]")
      (description "RESISTOR, CHIP 1206 1K OHM 1% 1/4W THICK FILM ROHS")
      (fields
        (field (name "MFG") "PANASONIC")
        (field (name "TOLERANCE") "1%")
        (field (name "POWER") ".25W")
        (field (name "Comment") "CDERA00195")
        (field (name "PUBLISHER") "Altium Limited")
      )
      (libsource (lib "HabLib") (part "CDERA00195"))
    )
    (comp (ref "R56")
      (value "300K")
      (footprint "HABLIB:3216[1206]")
      (description "RESISTOR, CHIP 1206 300K OHM 1% 1/4W THICK FILM ROHS")
      (fields
        (field (name "MFG") "PANASONIC")
        (field (name "TOLERANCE") "1%")
        (field (name "POWER") ".25W")
        (field (name "Comment") "CDERA00275_8")
        (field (name "PUBLISHER") "Altium Limited")
      )
      (libsource (lib "HabLib") (part "CDERA00275_8"))
    )
    (comp (ref "SW3")
      (value "CDESA00095_1")
      (footprint "COPAL_CSS-1210MC")
      (description "SWITCH, SPST, SLIDE, TH")
      (fields (field (name "MFG") "COPAL ELECTRONICS") (field (name "MFG_PN") "CSS-1210MC"))
      (libsource (lib "HabLib") (part "CDESA00095_1"))
    )
    (comp (ref "U7")
      (value "STMPE24M31")
      (footprint "QFN40P500X500X80-41V_MODIFIED")
      (description "IC, TOUCHKEY CONTROLLER, 24CH, I2C, 40QFN")
      (fields
        (field (name "MFG") "ST")
        (field (name "Comment") "CDEUA00052_1")
        (field (name "PUBLISHER") "Altium Limited")
      )
      (libsource (lib "HabLib") (part "CDEUA00052_1"))
    )
    (comp (ref "U8")
      (value "STMPE24M31")
      (footprint "QFN40P500X500X80-41V_MODIFIED")
      (description "IC, TOUCHKEY CONTROLLER, 24CH, I2C, 40QFN")
      (fields
        (field (name "MFG") "ST")
        (field (name "Comment") "CDEUA00052_1")
        (field (name "PUBLISHER") "Altium Limited")
      )
      (libsource (lib "HabLib") (part "CDEUA00052_1"))
    )
    (comp (ref "U9")
      (value "LM2842X")
      (footprint "TSOT6")
      (description "IC, BUCK REGULATOR, 0.6A, TSOT23-6")
      (fields (field (name "MFG") "NATIONAL SEMICONDUCTOR") (field (name "Comment") "CDEUA00014_1"))
      (libsource (lib "HabLib") (part "CDEUA00014_1"))
    )
  )
  (nets
    (net (code "1") (name "/ACAP0") (class "Default")
      (node (ref "CS37") (pin "1") (pinfunction "1_1") (pintype "passive"))
      (node (ref "U7") (pin "1") (pinfunction "CAP0_1") (pintype "passive"))
    )
    (net (code "2") (name "/ACAP1") (class "Default")
      (node (ref "CS27") (pin "1") (pinfunction "1_1") (pintype "passive"))
      (node (ref "U7") (pin "2") (pinfunction "CAP1_2") (pintype "passive"))
    )
    (net (code "3") (name "/ACAP2") (class "Default")
      (node (ref "CS26") (pin "1") (pinfunction "1_1") (pintype "passive"))
      (node (ref "U7") (pin "3") (pinfunction "CAP2_3") (pintype "passive"))
    )
    (net (code "4") (name "/ACAP3") (class "Default")
      (node (ref "CS14") (pin "1") (pinfunction "1_1") (pintype "passive"))
      (node (ref "U7") (pin "8") (pinfunction "CAP3_8") (pintype "passive"))
    )
    (net (code "5") (name "/ACAP4") (class "Default")
      (node (ref "CS15") (pin "1") (pinfunction "1_1") (pintype "passive"))
      (node (ref "U7") (pin "9") (pinfunction "CAP4_9") (pintype "passive"))
    )
    (net (code "6") (name "/ACAP5") (class "Default")
      (node (ref "CS1") (pin "1") (pinfunction "1_1") (pintype "passive"))
      (node (ref "U7") (pin "10") (pinfunction "CAP5_10") (pintype "passive"))
    )
    (net (code "7") (name "/ACAP6") (class "Default")
      (node (ref "CS2") (pin "1") (pinfunction "1_1") (pintype "passive"))
      (node (ref "U7") (pin "11") (pinfunction "CAP6_11") (pintype "passive"))
    )
    (net (code "8") (name "/ACAP7") (class "Default")
      (node (ref "CS3") (pin "1") (pinfunction "1_1") (pintype "passive"))
      (node (ref "U7") (pin "12") (pinfunction "CAP7_12") (pintype "passive"))
    )
    (net (code "9") (name "/ACAP8") (class "Default")
      (node (ref "CS17") (pin "1") (pinfunction "1_1") (pintype "passive"))
      (node (ref "U7") (pin "28") (pinfunction "CAP8_28") (pintype "passive"))
    )
    (net (code "10") (name "/ACAP9") (class "Default")
      (node (ref "CS18") (pin "1") (pinfunction "1_1") (pintype "passive"))
      (node (ref "U7") (pin "29") (pinfunction "CAP9_29") (pintype "passive"))
    )
    (net (code "11") (name "/ACAP10") (class "Default")
      (node (ref "CS30") (pin "1") (pinfunction "1_1") (pintype "passive"))
      (node (ref "U7") (pin "31") (pinfunction "CAP10_31") (pintype "passive"))
    )
    (net (code "12") (name "/ACAP11") (class "Default")
      (node (ref "CS29") (pin "1") (pinfunction "1_1") (pintype "passive"))
      (node (ref "U7") (pin "32") (pinfunction "CAP11_32") (pintype "passive"))
    )
    (net (code "13") (name "/ACAP12") (class "Default")
      (node (ref "CS28") (pin "1") (pinfunction "1_1") (pintype "passive"))
      (node (ref "U7") (pin "33") (pinfunction "CAP12_33") (pintype "passive"))
    )
    (net (code "14") (name "/ACAP13") (class "Default")
      (node (ref "CS42") (pin "1") (pinfunction "1_1") (pintype "passive"))
      (node (ref "U7") (pin "34") (pinfunction "CAP13_34") (pintype "passive"))
    )
    (net (code "15") (name "/ACAP14") (class "Default")
      (node (ref "CS39") (pin "1") (pinfunction "1_1") (pintype "passive"))
      (node (ref "U7") (pin "39") (pinfunction "CAP14_39") (pintype "passive"))
    )
    (net (code "16") (name "/ACAP15") (class "Default")
      (node (ref "CS38") (pin "1") (pinfunction "1_1") (pintype "passive"))
      (node (ref "U7") (pin "40") (pinfunction "CAP15_40") (pintype "passive"))
    )
    (net (code "17") (name "/ACAP16") (class "Default")
      (node (ref "CS25") (pin "1") (pinfunction "1_1") (pintype "passive"))
      (node (ref "U7") (pin "6") (pinfunction "CAP16_6") (pintype "passive"))
    )
    (net (code "18") (name "/ACAP17") (class "Default")
      (node (ref "CS13") (pin "1") (pinfunction "1_1") (pintype "passive"))
      (node (ref "U7") (pin "7") (pinfunction "CAP17_7") (pintype "passive"))
    )
    (net (code "19") (name "/ACAP18") (class "Default")
      (node (ref "CS4") (pin "1") (pinfunction "1_1") (pintype "passive"))
      (node (ref "U7") (pin "15") (pinfunction "CAP18_15") (pintype "passive"))
    )
    (net (code "20") (name "/ACAP19") (class "Default")
      (node (ref "CS5") (pin "1") (pinfunction "1_1") (pintype "passive"))
      (node (ref "U7") (pin "16") (pinfunction "CAP19_16") (pintype "passive"))
    )
    (net (code "21") (name "/ACAP20") (class "Default")
      (node (ref "CS6") (pin "1") (pinfunction "1_1") (pintype "passive"))
      (node (ref "U7") (pin "25") (pinfunction "CAP20_25") (pintype "passive"))
    )
    (net (code "22") (name "/ACAP21") (class "Default")
      (node (ref "CS16") (pin "1") (pinfunction "1_1") (pintype "passive"))
      (node (ref "U7") (pin "26") (pinfunction "CAP21_26") (pintype "passive"))
    )
    (net (code "23") (name "/ACAP22") (class "Default")
      (node (ref "CS41") (pin "1") (pinfunction "1_1") (pintype "passive"))
      (node (ref "U7") (pin "37") (pinfunction "CPA22_37") (pintype "passive"))
    )
    (net (code "24") (name "/ACAP23") (class "Default")
      (node (ref "CS40") (pin "1") (pinfunction "1_1") (pintype "passive"))
      (node (ref "U7") (pin "38") (pinfunction "CAP23_38") (pintype "passive"))
    )
    (net (code "25") (name "/ADC_BAT") (class "Default")
      (node (ref "C40") (pin "1") (pinfunction "1_1") (pintype "passive"))
      (node (ref "R37") (pin "1") (pinfunction "1_1") (pintype "passive"))
      (node (ref "R39") (pin "2") (pinfunction "2_2") (pintype "passive"))
    )
    (net (code "26") (name "/ADC_METER") (class "Default")
      (node (ref "C44") (pin "1") (pinfunction "1_1") (pintype "passive"))
      (node (ref "D19") (pin "1") (pinfunction "A_1") (pintype "passive"))
      (node (ref "D21") (pin "2") (pinfunction "K_2") (pintype "passive"))
      (node (ref "R31") (pin "2") (pinfunction "2_2") (pintype "passive"))
      (node (ref "R42") (pin "2") (pinfunction "2_2") (pintype "passive"))
      (node (ref "R47") (pin "2") (pinfunction "2_2") (pintype "passive"))
      (node (ref "R48") (pin "2") (pinfunction "2_2") (pintype "passive"))
      (node (ref "R49") (pin "2") (pinfunction "2_2") (pintype "passive"))
    )
    (net (code "27") (name "/BAT_CON") (class "Default")
      (node (ref "Q18") (pin "1") (pinfunction "B_1") (pintype "passive"))
      (node (ref "Q4") (pin "1") (pinfunction "B_1") (pintype "passive"))
      (node (ref "Q5") (pin "1") (pinfunction "B_1") (pintype "passive"))
      (node (ref "Q9") (pin "3") (pinfunction "C_3") (pintype "passive"))
      (node (ref "R44") (pin "1") (pinfunction "1_1") (pintype "passive"))
    )
    (net (code "28") (name "/BCAP0") (class "Default")
      (node (ref "CS34") (pin "1") (pinfunction "1_1") (pintype "passive"))
      (node (ref "U8") (pin "1") (pinfunction "CAP0_1") (pintype "passive"))
    )
    (net (code "29") (name "/BCAP1") (class "Default")
      (node (ref "CS35") (pin "1") (pinfunction "1_1") (pintype "passive"))
      (node (ref "U8") (pin "2") (pinfunction "CAP1_2") (pintype "passive"))
    )
    (net (code "30") (name "/BCAP2") (class "Default")
      (node (ref "CS47") (pin "1") (pinfunction "1_1") (pintype "passive"))
      (node (ref "U8") (pin "3") (pinfunction "CAP2_3") (pintype "passive"))
    )
    (net (code "31") (name "/BCAP3") (class "Default")
      (node (ref "CS44") (pin "1") (pinfunction "1_1") (pintype "passive"))
      (node (ref "U8") (pin "8") (pinfunction "CAP3_8") (pintype "passive"))
    )
    (net (code "32") (name "/BCAP4") (class "Default")
      (node (ref "CS32") (pin "1") (pinfunction "1_1") (pintype "passive"))
      (node (ref "U8") (pin "9") (pinfunction "CAP4_9") (pintype "passive"))
    )
    (net (code "33") (name "/BCAP5") (class "Default")
      (node (ref "CS43") (pin "1") (pinfunction "1_1") (pintype "passive"))
      (node (ref "U8") (pin "10") (pinfunction "CAP5_10") (pintype "passive"))
    )
    (net (code "34") (name "/BCAP6") (class "Default")
      (node (ref "CS19") (pin "1") (pinfunction "1_1") (pintype "passive"))
      (node (ref "U8") (pin "11") (pinfunction "CAP6_11") (pintype "passive"))
    )
    (net (code "35") (name "/BCAP7") (class "Default")
      (node (ref "CS20") (pin "1") (pinfunction "1_1") (pintype "passive"))
      (node (ref "U8") (pin "12") (pinfunction "CAP7_12") (pintype "passive"))
    )
    (net (code "36") (name "/BCAP8") (class "Default")
      (node (ref "CS31") (pin "1") (pinfunction "1_1") (pintype "passive"))
      (node (ref "U8") (pin "28") (pinfunction "CAP8_28") (pintype "passive"))
    )
    (net (code "37") (name "/BCAP9") (class "Default")
      (node (ref "CS36") (pin "1") (pinfunction "1_1") (pintype "passive"))
      (node (ref "U8") (pin "29") (pinfunction "CAP9_29") (pintype "passive"))
    )
    (net (code "38") (name "/BCAP10") (class "Default")
      (node (ref "CS48") (pin "1") (pinfunction "1_1") (pintype "passive"))
      (node (ref "U8") (pin "31") (pinfunction "CAP10_31") (pintype "passive"))
    )
    (net (code "39") (name "/BCAP11") (class "Default")
      (node (ref "CS9") (pin "1") (pinfunction "1_1") (pintype "passive"))
      (node (ref "U8") (pin "32") (pinfunction "CAP11_32") (pintype "passive"))
    )
    (net (code "40") (name "/BCAP12") (class "Default")
      (node (ref "CS10") (pin "1") (pinfunction "1_1") (pintype "passive"))
      (node (ref "U8") (pin "33") (pinfunction "CAP12_33") (pintype "passive"))
    )
    (net (code "41") (name "/BCAP13") (class "Default")
      (node (ref "CS11") (pin "1") (pinfunction "1_1") (pintype "passive"))
      (node (ref "U8") (pin "34") (pinfunction "CAP13_34") (pintype "passive"))
    )
    (net (code "42") (name "/BCAP14") (class "Default")
      (node (ref "CS23") (pin "1") (pinfunction "1_1") (pintype "passive"))
      (node (ref "U8") (pin "39") (pinfunction "CAP14_39") (pintype "passive"))
    )
    (net (code "43") (name "/BCAP15") (class "Default")
      (node (ref "CS33") (pin "1") (pinfunction "1_1") (pintype "passive"))
      (node (ref "U8") (pin "40") (pinfunction "CAP15_40") (pintype "passive"))
    )
    (net (code "44") (name "/BCAP16") (class "Default")
      (node (ref "CS46") (pin "1") (pinfunction "1_1") (pintype "passive"))
      (node (ref "U8") (pin "6") (pinfunction "CAP16_6") (pintype "passive"))
    )
    (net (code "45") (name "/BCAP17") (class "Default")
      (node (ref "CS45") (pin "1") (pinfunction "1_1") (pintype "passive"))
      (node (ref "U8") (pin "7") (pinfunction "CAP17_7") (pintype "passive"))
    )
    (net (code "46") (name "/BCAP18") (class "Default")
      (node (ref "CS7") (pin "1") (pinfunction "1_1") (pintype "passive"))
      (node (ref "U8") (pin "15") (pinfunction "CAP18_15") (pintype "passive"))
    )
    (net (code "47") (name "/BCAP19") (class "Default")
      (node (ref "CS8") (pin "1") (pinfunction "1_1") (pintype "passive"))
      (node (ref "U8") (pin "16") (pinfunction "CAP19_16") (pintype "passive"))
    )
    (net (code "48") (name "/BCAP20") (class "Default")
      (node (ref "CS12") (pin "1") (pinfunction "1_1") (pintype "passive"))
      (node (ref "U8") (pin "25") (pinfunction "CAP20_25") (pintype "passive"))
    )
    (net (code "49") (name "/BCAP21") (class "Default")
      (node (ref "CS24") (pin "1") (pinfunction "1_1") (pintype "passive"))
      (node (ref "U8") (pin "26") (pinfunction "CAP21_26") (pintype "passive"))
    )
    (net (code "50") (name "/BCAP22") (class "Default")
      (node (ref "CS21") (pin "1") (pinfunction "1_1") (pintype "passive"))
      (node (ref "U8") (pin "37") (pinfunction "CPA22_37") (pintype "passive"))
    )
    (net (code "51") (name "/BCAP23") (class "Default")
      (node (ref "CS22") (pin "1") (pinfunction "1_1") (pintype "passive"))
      (node (ref "U8") (pin "38") (pinfunction "CAP23_38") (pintype "passive"))
    )
    (net (code "52") (name "/INT_ACAP") (class "Default")
      (node (ref "R29") (pin "1") (pinfunction "1_1") (pintype "passive"))
      (node (ref "U7") (pin "18") (pinfunction "INT_18") (pintype "passive"))
    )
    (net (code "53") (name "/INT_BCAP") (class "Default")
      (node (ref "R30") (pin "1") (pinfunction "1_1") (pintype "passive"))
      (node (ref "U8") (pin "18") (pinfunction "INT_18") (pintype "passive"))
    )
    (net (code "54") (name "/PWM_BL") (class "Default")
      (node (ref "Q6") (pin "1") (pinfunction "B_1") (pintype "passive"))
    )
    (net (code "55") (name "/RNG_10") (class "Default")
      (node (ref "Q11") (pin "1") (pinfunction "B_1") (pintype "passive"))
    )
    (net (code "56") (name "/RNG_20") (class "Default")
      (node (ref "Q12") (pin "1") (pinfunction "B_1") (pintype "passive"))
    )
    (net (code "57") (name "/RNG_30") (class "Default")
      (node (ref "Q13") (pin "1") (pinfunction "B_1") (pintype "passive"))
    )
    (net (code "58") (name "/SCL0") (class "Default")
      (node (ref "U7") (pin "20") (pinfunction "SCL_20") (pintype "passive"))
      (node (ref "U8") (pin "20") (pinfunction "SCL_20") (pintype "passive"))
    )
    (net (code "59") (name "/SDA0") (class "Default")
      (node (ref "U7") (pin "21") (pinfunction "SDA_21") (pintype "passive"))
      (node (ref "U8") (pin "21") (pinfunction "SDA_21") (pintype "passive"))
    )
    (net (code "60") (name "/SEL_V{slash}~{C}") (class "Default")
      (node (ref "Q16") (pin "1") (pinfunction "B_1") (pintype "passive"))
      (node (ref "Q8") (pin "1") (pinfunction "B_1") (pintype "passive"))
      (node (ref "R56") (pin "1") (pinfunction "1_1") (pintype "passive"))
    )
    (net (code "61") (name "/SYS_RST") (class "Default")
      (node (ref "U7") (pin "22") (pinfunction "RST_22") (pintype "passive"))
      (node (ref "U8") (pin "22") (pinfunction "RST_22") (pintype "passive"))
    )
    (net (code "62") (name "/VREF30") (class "Default")
      (node (ref "Q10") (pin "2") (pinfunction "E_2") (pintype "passive"))
      (node (ref "R54") (pin "2") (pinfunction "2_2") (pintype "passive"))
    )
    (net (code "63") (name "3.3V") (class "Default")
      (node (ref "C29") (pin "1") (pinfunction "1_1") (pintype "passive"))
      (node (ref "C30") (pin "1") (pinfunction "1_1") (pintype "passive"))
      (node (ref "C31") (pin "1") (pinfunction "1_1") (pintype "passive"))
      (node (ref "C32") (pin "1") (pinfunction "1_1") (pintype "passive"))
      (node (ref "C33") (pin "1") (pinfunction "1_1") (pintype "passive"))
      (node (ref "C34") (pin "1") (pinfunction "1_1") (pintype "passive"))
      (node (ref "C35") (pin "1") (pinfunction "1_1") (pintype "passive"))
      (node (ref "C36") (pin "1") (pinfunction "1_1") (pintype "passive"))
      (node (ref "C38") (pin "1") (pinfunction "1_1") (pintype "passive"))
      (node (ref "C39") (pin "1") (pinfunction "1_1") (pintype "passive"))
      (node (ref "D19") (pin "2") (pinfunction "K_2") (pintype "passive"))
      (node (ref "L1") (pin "2") (pinfunction "2_2") (pintype "passive"))
      (node (ref "R29") (pin "2") (pinfunction "2_2") (pintype "passive"))
      (node (ref "R30") (pin "2") (pinfunction "2_2") (pintype "passive"))
      (node (ref "R33") (pin "2") (pinfunction "2_2") (pintype "passive"))
      (node (ref "R40") (pin "2") (pinfunction "2_2") (pintype "passive"))
      (node (ref "R56") (pin "2") (pinfunction "2_2") (pintype "passive"))
      (node (ref "U7") (pin "14") (pinfunction "VIO_14") (pintype "passive"))
      (node (ref "U7") (pin "30") (pinfunction "VIO_30") (pintype "passive"))
      (node (ref "U7") (pin "35") (pinfunction "VIO_35") (pintype "passive"))
      (node (ref "U7") (pin "5") (pinfunction "VIO_5") (pintype "passive"))
      (node (ref "U8") (pin "14") (pinfunction "VIO_14") (pintype "passive"))
      (node (ref "U8") (pin "19") (pinfunction "ADDR0_19") (pintype "passive"))
      (node (ref "U8") (pin "30") (pinfunction "VIO_30") (pintype "passive"))
      (node (ref "U8") (pin "35") (pinfunction "VIO_35") (pintype "passive"))
      (node (ref "U8") (pin "5") (pinfunction "VIO_5") (pintype "passive"))
    )
    (net (code "64") (name "6V") (class "Default")
      (node (ref "Q18") (pin "2") (pinfunction "E_2") (pintype "passive"))
      (node (ref "Q4") (pin "2") (pinfunction "E_2") (pintype "passive"))
      (node (ref "R37") (pin "2") (pinfunction "2_2") (pintype "passive"))
      (node (ref "R43") (pin "2") (pinfunction "2_2") (pintype "passive"))
      (node (ref "R44") (pin "2") (pinfunction "2_2") (pintype "passive"))
      (node (ref "SW3") (pin "3") (pintype "passive"))
    )
    (net (code "65") (name "GND") (class "Default")
      (node (ref "BAT2") (pin "2") (pinfunction "2_2") (pintype "passive"))
      (node (ref "C25") (pin "2") (pinfunction "2_2") (pintype "passive"))
      (node (ref "C26") (pin "2") (pinfunction "2_2") (pintype "passive"))
      (node (ref "C27") (pin "2") (pinfunction "2_2") (pintype "passive"))
      (node (ref "C28") (pin "2") (pinfunction "2_2") (pintype "passive"))
      (node (ref "C29") (pin "2") (pinfunction "2_2") (pintype "passive"))
      (node (ref "C30") (pin "2") (pinfunction "2_2") (pintype "passive"))
      (node (ref "C31") (pin "2") (pinfunction "2_2") (pintype "passive"))
      (node (ref "C32") (pin "2") (pinfunction "2_2") (pintype "passive"))
      (node (ref "C33") (pin "2") (pinfunction "2_2") (pintype "passive"))
      (node (ref "C34") (pin "2") (pinfunction "2_2") (pintype "passive"))
      (node (ref "C35") (pin "2") (pinfunction "2_2") (pintype "passive"))
      (node (ref "C36") (pin "2") (pinfunction "2_2") (pintype "passive"))
      (node (ref "C38") (pin "2") (pinfunction "2_2") (pintype "passive"))
      (node (ref "C39") (pin "2") (pinfunction "2_2") (pintype "passive"))
      (node (ref "C40") (pin "2") (pinfunction "2_2") (pintype "passive"))
      (node (ref "C41") (pin "1") (pinfunction "1_1") (pintype "passive"))
      (node (ref "C42") (pin "2") (pinfunction "2_2") (pintype "passive"))
      (node (ref "C43") (pin "2") (pinfunction "2_2") (pintype "passive"))
      (node (ref "C46") (pin "2") (pinfunction "2_2") (pintype "passive"))
      (node (ref "D18") (pin "1") (pinfunction "A_1") (pintype "passive"))
      (node (ref "FB5") (pin "1") (pinfunction "1_1") (pintype "passive"))
      (node (ref "Q17") (pin "2") (pinfunction "E_2") (pintype "passive"))
      (node (ref "Q6") (pin "2") (pinfunction "E_2") (pintype "passive"))
      (node (ref "Q9") (pin "2") (pinfunction "E_2") (pintype "passive"))
      (node (ref "R39") (pin "1") (pinfunction "1_1") (pintype "passive"))
      (node (ref "R45") (pin "1") (pinfunction "1_1") (pintype "passive"))
      (node (ref "R46") (pin "1") (pinfunction "1_1") (pintype "passive"))
      (node (ref "U7") (pin "13") (pinfunction "GND_13") (pintype "passive"))
      (node (ref "U7") (pin "19") (pinfunction "ADDR0_19") (pintype "passive"))
      (node (ref "U7") (pin "23") (pinfunction "ADDR1_23") (pintype "passive"))
      (node (ref "U7") (pin "27") (pinfunction "GND_27") (pintype "passive"))
      (node (ref "U7") (pin "36") (pinfunction "GND_36") (pintype "passive"))
      (node (ref "U7") (pin "4") (pinfunction "GND_4") (pintype "passive"))
      (node (ref "U8") (pin "13") (pinfunction "GND_13") (pintype "passive"))
      (node (ref "U8") (pin "23") (pinfunction "ADDR1_23") (pintype "passive"))
      (node (ref "U8") (pin "27") (pinfunction "GND_27") (pintype "passive"))
      (node (ref "U8") (pin "36") (pinfunction "GND_36") (pintype "passive"))
      (node (ref "U8") (pin "4") (pinfunction "GND_4") (pintype "passive"))
      (node (ref "U9") (pin "2") (pinfunction "GND_2") (pintype "passive"))
    )
    (net (code "66") (name "GNDA") (class "Default")
      (node (ref "C44") (pin "2") (pinfunction "2_2") (pintype "passive"))
      (node (ref "D21") (pin "1") (pinfunction "A_1") (pintype "passive"))
      (node (ref "FB5") (pin "2") (pinfunction "2_2") (pintype "passive"))
      (node (ref "Q11") (pin "2") (pinfunction "E_2") (pintype "passive"))
      (node (ref "Q12") (pin "2") (pinfunction "E_2") (pintype "passive"))
      (node (ref "Q13") (pin "2") (pinfunction "E_2") (pintype "passive"))
      (node (ref "Q15") (pin "2") (pinfunction "E_2") (pintype "passive"))
      (node (ref "Q16") (pin "2") (pinfunction "E_2") (pintype "passive"))
      (node (ref "Q7") (pin "2") (pinfunction "E_2") (pintype "passive"))
      (node (ref "Q8") (pin "2") (pinfunction "E_2") (pintype "passive"))
    )
    (net (code "67") (name "Net-(BAT1-Pad2)") (class "Default")
      (node (ref "BAT1") (pin "2") (pinfunction "2_2") (pintype "passive"))
      (node (ref "BAT2") (pin "1") (pinfunction "1_1") (pintype "passive"))
    )
    (net (code "68") (name "Net-(D15-A)") (class "Default")
      (node (ref "D15") (pin "1") (pinfunction "A_1") (pintype "passive"))
      (node (ref "Q2") (pin "1") (pinfunction "B_1") (pintype "passive"))
      (node (ref "R34") (pin "2") (pinfunction "2_2") (pintype "passive"))
      (node (ref "R35") (pin "1") (pinfunction "1_1") (pintype "passive"))
    )
    (net (code "69") (name "Net-(D15-K)") (class "Default")
      (node (ref "C45") (pin "1") (pinfunction "1_1") (pintype "passive"))
      (node (ref "D15") (pin "3") (pinfunction "K_3") (pintype "passive"))
      (node (ref "J5") (pin "1") (pinfunction "1_1") (pintype "passive"))
      (node (ref "Q2") (pin "2") (pinfunction "E_2") (pintype "passive"))
      (node (ref "R34") (pin "1") (pinfunction "1_1") (pintype "passive"))
      (node (ref "R41") (pin "1") (pinfunction "1_1") (pintype "passive"))
    )
    (net (code "70") (name "Net-(D16-A)") (class "Default")
      (node (ref "D16") (pin "1") (pinfunction "A_1") (pintype "passive"))
      (node (ref "R32") (pin "1") (pinfunction "1_1") (pintype "passive"))
    )
    (net (code "71") (name "Net-(D16-K)") (class "Default")
      (node (ref "D16") (pin "2") (pinfunction "K_2") (pintype "passive"))
      (node (ref "D17") (pin "2") (pinfunction "K_2") (pintype "passive"))
      (node (ref "Q3") (pin "2") (pinfunction "E_2") (pintype "passive"))
      (node (ref "R36") (pin "2") (pinfunction "2_2") (pintype "passive"))
    )
    (net (code "72") (name "Net-(D17-A)") (class "Default")
      (node (ref "D17") (pin "1") (pinfunction "A_1") (pintype "passive"))
      (node (ref "R38") (pin "2") (pinfunction "2_2") (pintype "passive"))
    )
    (net (code "73") (name "Net-(D18-K)") (class "Default")
      (node (ref "C37") (pin "2") (pinfunction "2_2") (pintype "passive"))
      (node (ref "D18") (pin "2") (pinfunction "K_2") (pintype "passive"))
      (node (ref "L1") (pin "1") (pinfunction "1_1") (pintype "passive"))
      (node (ref "U9") (pin "6") (pinfunction "SW_6") (pintype "passive"))
    )
    (net (code "74") (name "Net-(D20-A)") (class "Default")
      (node (ref "D20") (pin "1") (pinfunction "A_1") (pintype "passive"))
      (node (ref "D22") (pin "1") (pinfunction "A_1") (pintype "passive"))
    )
    (net (code "75") (name "Net-(D20-K)") (class "Default")
      (node (ref "D20") (pin "3") (pinfunction "K_3") (pintype "passive"))
      (node (ref "R41") (pin "2") (pinfunction "2_2") (pintype "passive"))
      (node (ref "R42") (pin "1") (pinfunction "1_1") (pintype "passive"))
    )
    (net (code "76") (name "Net-(D22-K)") (class "Default")
      (node (ref "C45") (pin "2") (pinfunction "2_2") (pintype "passive"))
      (node (ref "D22") (pin "3") (pinfunction "K_3") (pintype "passive"))
      (node (ref "J5") (pin "2") (pinfunction "2_2") (pintype "passive"))
      (node (ref "Q16") (pin "3") (pinfunction "C_3") (pintype "passive"))
      (node (ref "R50") (pin "1") (pinfunction "1_1") (pintype "passive"))
    )
    (net (code "77") (name "Net-(D23-A)") (class "Default")
      (node (ref "D23") (pin "1") (pinfunction "A_1") (pintype "passive"))
      (node (ref "Q14") (pin "2") (pinfunction "E_2") (pintype "passive"))
    )
    (net (code "78") (name "Net-(Q2-C)") (class "Default")
      (node (ref "Q2") (pin "3") (pinfunction "C_3") (pintype "passive"))
      (node (ref "R31") (pin "1") (pinfunction "1_1") (pintype "passive"))
    )
    (net (code "79") (name "Net-(Q3-B)") (class "Default")
      (node (ref "Q3") (pin "1") (pinfunction "B_1") (pintype "passive"))
      (node (ref "Q6") (pin "3") (pinfunction "C_3") (pintype "passive"))
      (node (ref "R36") (pin "1") (pinfunction "1_1") (pintype "passive"))
    )
    (net (code "80") (name "Net-(Q4-C)") (class "Default")
      (node (ref "Q4") (pin "3") (pinfunction "C_3") (pintype "passive"))
      (node (ref "Q5") (pin "3") (pinfunction "C_3") (pintype "passive"))
    )
    (net (code "81") (name "Net-(Q7-C)") (class "Default")
      (node (ref "Q7") (pin "3") (pinfunction "C_3") (pintype "passive"))
      (node (ref "R35") (pin "2") (pinfunction "2_2") (pintype "passive"))
    )
    (net (code "82") (name "Net-(Q10-B)") (class "Default")
      (node (ref "Q10") (pin "1") (pinfunction "B_1") (pintype "passive"))
      (node (ref "R54") (pin "1") (pinfunction "1_1") (pintype "passive"))
      (node (ref "R55") (pin "2") (pinfunction "2_2") (pintype "passive"))
    )
    (net (code "83") (name "Net-(Q10-C)") (class "Default")
      (node (ref "Q10") (pin "3") (pinfunction "C_3") (pintype "passive"))
      (node (ref "R50") (pin "2") (pinfunction "2_2") (pintype "passive"))
    )
    (net (code "84") (name "Net-(Q11-C)") (class "Default")
      (node (ref "Q11") (pin "3") (pinfunction "C_3") (pintype "passive"))
      (node (ref "R51") (pin "1") (pinfunction "1_1") (pintype "passive"))
    )
    (net (code "85") (name "Net-(Q12-C)") (class "Default")
      (node (ref "Q12") (pin "3") (pinfunction "C_3") (pintype "passive"))
      (node (ref "R52") (pin "1") (pinfunction "1_1") (pintype "passive"))
    )
    (net (code "86") (name "Net-(Q13-C)") (class "Default")
      (node (ref "Q13") (pin "3") (pinfunction "C_3") (pintype "passive"))
      (node (ref "R53") (pin "1") (pinfunction "1_1") (pintype "passive"))
    )
    (net (code "87") (name "Net-(Q14-B)") (class "Default")
      (node (ref "C41") (pin "2") (pinfunction "2_2") (pintype "passive"))
      (node (ref "Q14") (pin "1") (pinfunction "B_1") (pintype "passive"))
      (node (ref "Q17") (pin "3") (pinfunction "C_3") (pintype "passive"))
      (node (ref "Q9") (pin "1") (pinfunction "B_1") (pintype "passive"))
      (node (ref "R43") (pin "1") (pinfunction "1_1") (pintype "passive"))
    )
    (net (code "88") (name "Net-(Q15-B)") (class "Default")
      (node (ref "Q15") (pin "1") (pinfunction "B_1") (pintype "passive"))
      (node (ref "Q7") (pin "1") (pinfunction "B_1") (pintype "passive"))
      (node (ref "Q8") (pin "3") (pinfunction "C_3") (pintype "passive"))
      (node (ref "R33") (pin "1") (pinfunction "1_1") (pintype "passive"))
    )
    (net (code "89") (name "Net-(Q15-C)") (class "Default")
      (node (ref "Q15") (pin "3") (pinfunction "C_3") (pintype "passive"))
      (node (ref "R55") (pin "1") (pinfunction "1_1") (pintype "passive"))
    )
    (net (code "90") (name "Net-(Q18-C)") (class "Default")
      (node (ref "Q18") (pin "3") (pinfunction "C_3") (pintype "passive"))
      (node (ref "R32") (pin "2") (pinfunction "2_2") (pintype "passive"))
    )
    (net (code "91") (name "Net-(R47-Pad1)") (class "Default")
      (node (ref "R47") (pin "1") (pinfunction "1_1") (pintype "passive"))
      (node (ref "R51") (pin "2") (pinfunction "2_2") (pintype "passive"))
    )
    (net (code "92") (name "Net-(R48-Pad1)") (class "Default")
      (node (ref "R48") (pin "1") (pinfunction "1_1") (pintype "passive"))
      (node (ref "R52") (pin "2") (pinfunction "2_2") (pintype "passive"))
    )
    (net (code "93") (name "Net-(R49-Pad1)") (class "Default")
      (node (ref "R49") (pin "1") (pinfunction "1_1") (pintype "passive"))
      (node (ref "R53") (pin "2") (pinfunction "2_2") (pintype "passive"))
    )
    (net (code "94") (name "Net-(U7-CREF)") (class "Default")
      (node (ref "C25") (pin "1") (pinfunction "1_1") (pintype "passive"))
      (node (ref "U7") (pin "24") (pinfunction "CREF_24") (pintype "passive"))
    )
    (net (code "95") (name "Net-(U7-VCC)") (class "Default")
      (node (ref "C27") (pin "1") (pinfunction "1_1") (pintype "passive"))
      (node (ref "U7") (pin "17") (pinfunction "VCC_17") (pintype "passive"))
    )
    (net (code "96") (name "Net-(U8-CREF)") (class "Default")
      (node (ref "C26") (pin "1") (pinfunction "1_1") (pintype "passive"))
      (node (ref "U8") (pin "24") (pinfunction "CREF_24") (pintype "passive"))
    )
    (net (code "97") (name "Net-(U8-VCC)") (class "Default")
      (node (ref "C28") (pin "1") (pinfunction "1_1") (pintype "passive"))
      (node (ref "U8") (pin "17") (pinfunction "VCC_17") (pintype "passive"))
    )
    (net (code "98") (name "Net-(U9-CB)") (class "Default")
      (node (ref "C37") (pin "1") (pinfunction "1_1") (pintype "passive"))
      (node (ref "U9") (pin "1") (pinfunction "CB_1") (pintype "passive"))
    )
    (net (code "99") (name "Net-(U9-FB)") (class "Default")
      (node (ref "R40") (pin "1") (pinfunction "1_1") (pintype "passive"))
      (node (ref "R46") (pin "2") (pinfunction "2_2") (pintype "passive"))
      (node (ref "U9") (pin "3") (pinfunction "FB_3") (pintype "passive"))
    )
    (net (code "100") (name "VBL") (class "Default")
      (node (ref "Q3") (pin "3") (pinfunction "C_3") (pintype "passive"))
    )
    (net (code "101") (name "VCC") (class "Default")
      (node (ref "C42") (pin "1") (pinfunction "1_1") (pintype "passive"))
      (node (ref "C43") (pin "1") (pinfunction "1_1") (pintype "passive"))
      (node (ref "D23") (pin "2") (pinfunction "K_2") (pintype "passive"))
      (node (ref "Q5") (pin "2") (pinfunction "E_2") (pintype "passive"))
      (node (ref "U9") (pin "4") (pinfunction "SHDN_4") (pintype "passive"))
      (node (ref "U9") (pin "5") (pinfunction "VIN_5") (pintype "passive"))
    )
    (net (code "102") (name "VCELL") (class "Default")
      (node (ref "BAT1") (pin "1") (pinfunction "1_1") (pintype "passive"))
      (node (ref "SW3") (pin "2") (pintype "passive"))
    )
    (net (code "103") (name "VUSB") (class "Default")
      (node (ref "C46") (pin "1") (pinfunction "1_1") (pintype "passive"))
      (node (ref "Q14") (pin "3") (pinfunction "C_3") (pintype "passive"))
      (node (ref "Q17") (pin "1") (pinfunction "B_1") (pintype "passive"))
      (node (ref "R38") (pin "1") (pinfunction "1_1") (pintype "passive"))
      (node (ref "R45") (pin "2") (pinfunction "2_2") (pintype "passive"))
    )
    (net (code "104") (name "unconnected-(SW3-Pad1)") (class "Default")
      (node (ref "SW3") (pin "1") (pintype "passive"))
    )
  )
)
